# E103-W02.net
KiCad netlist of a schematic drawn in Altium Designer
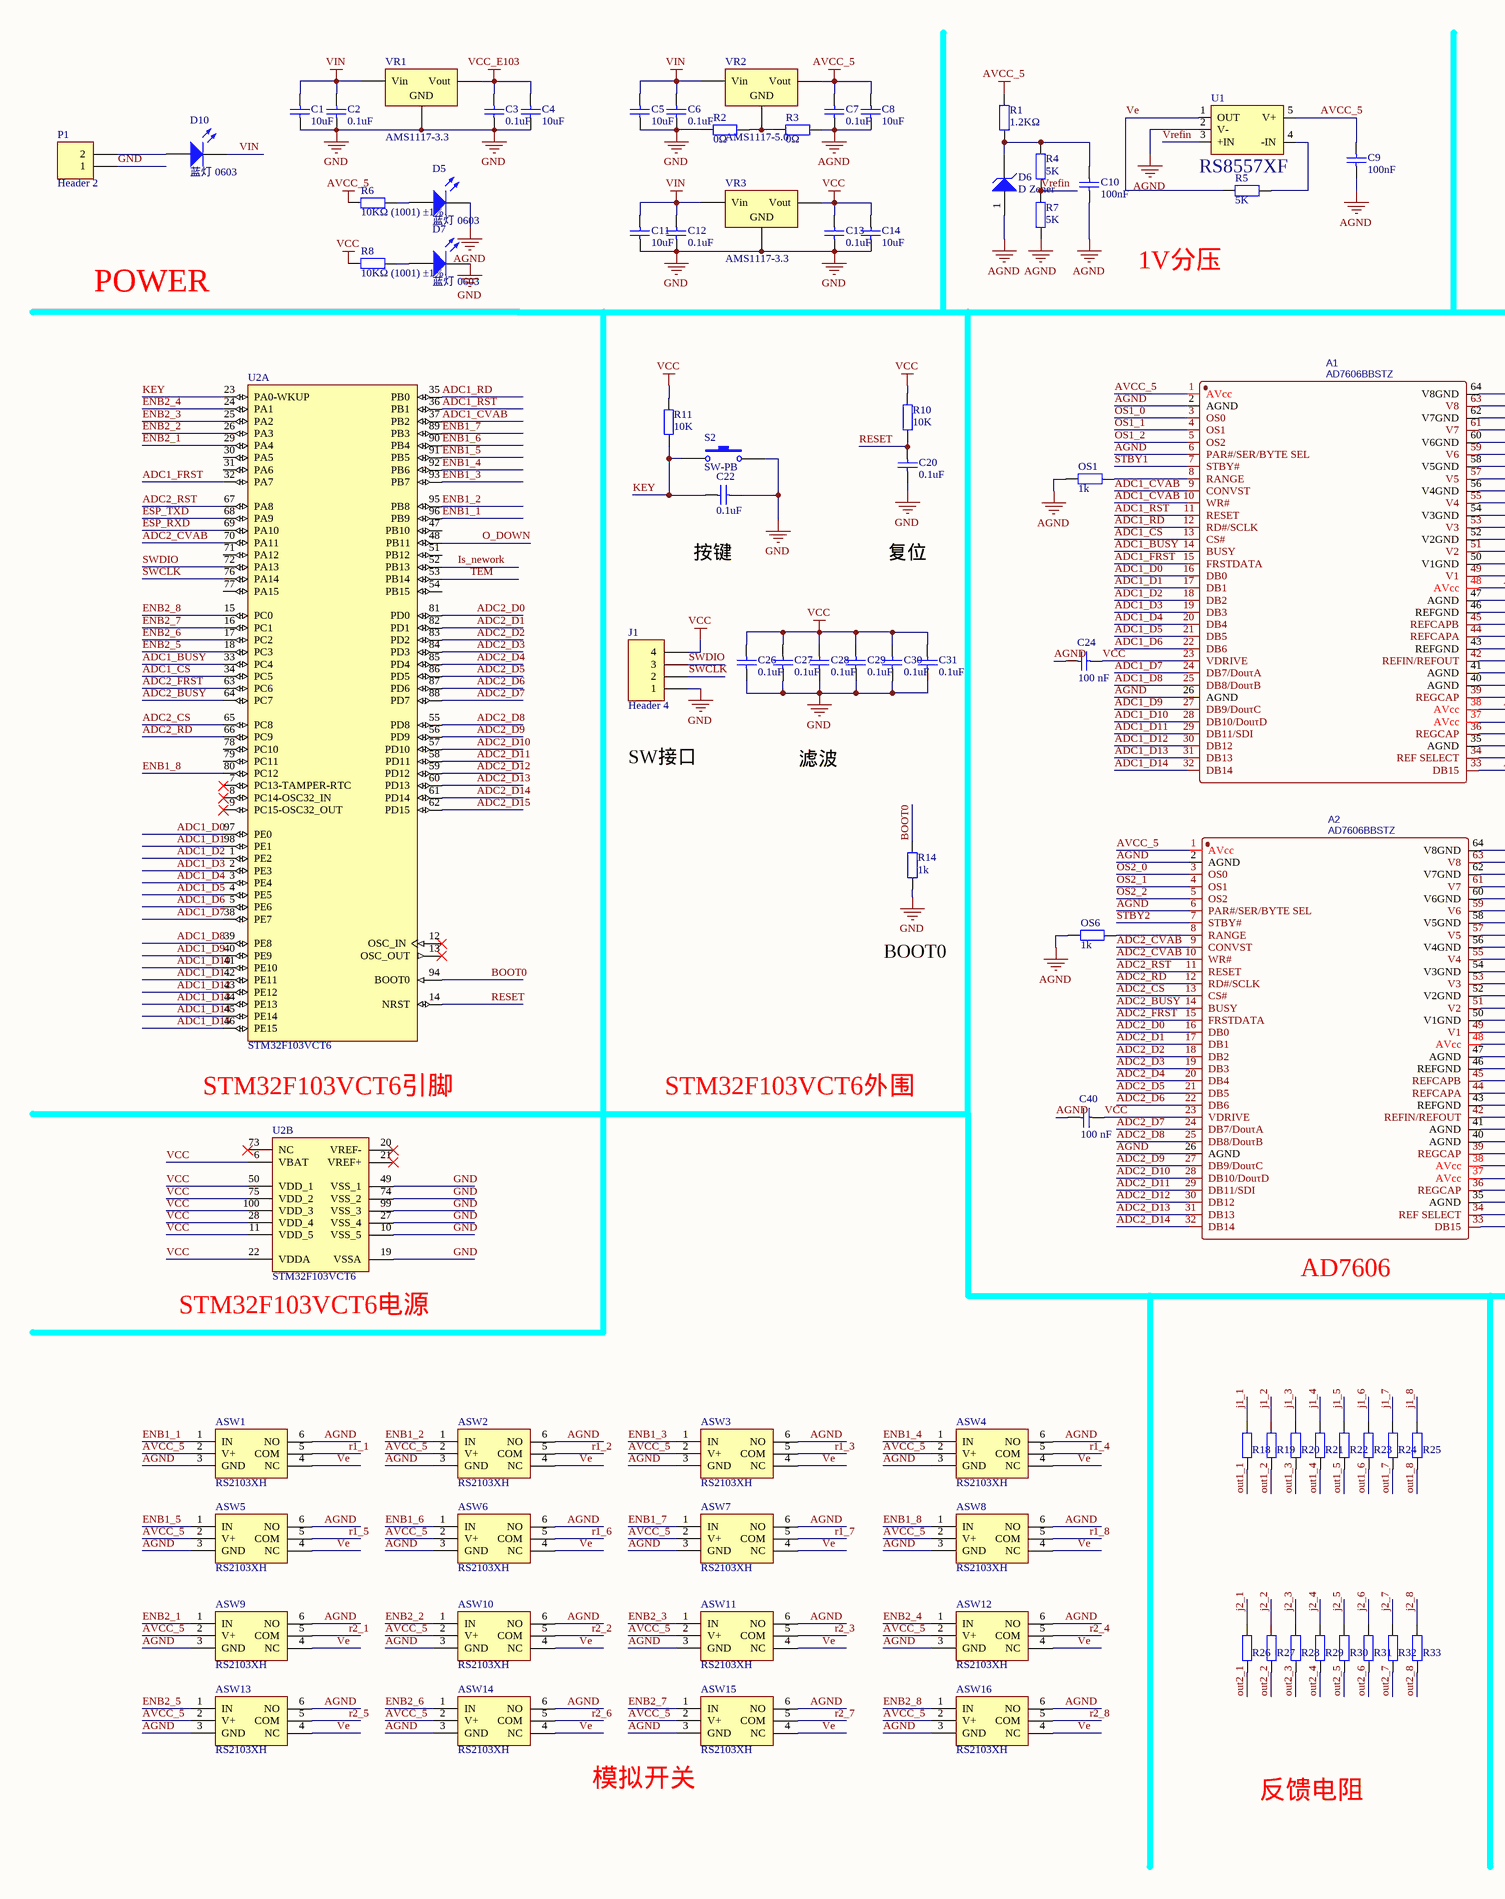
[diagram p0: E103-W02.SchDoc, left]
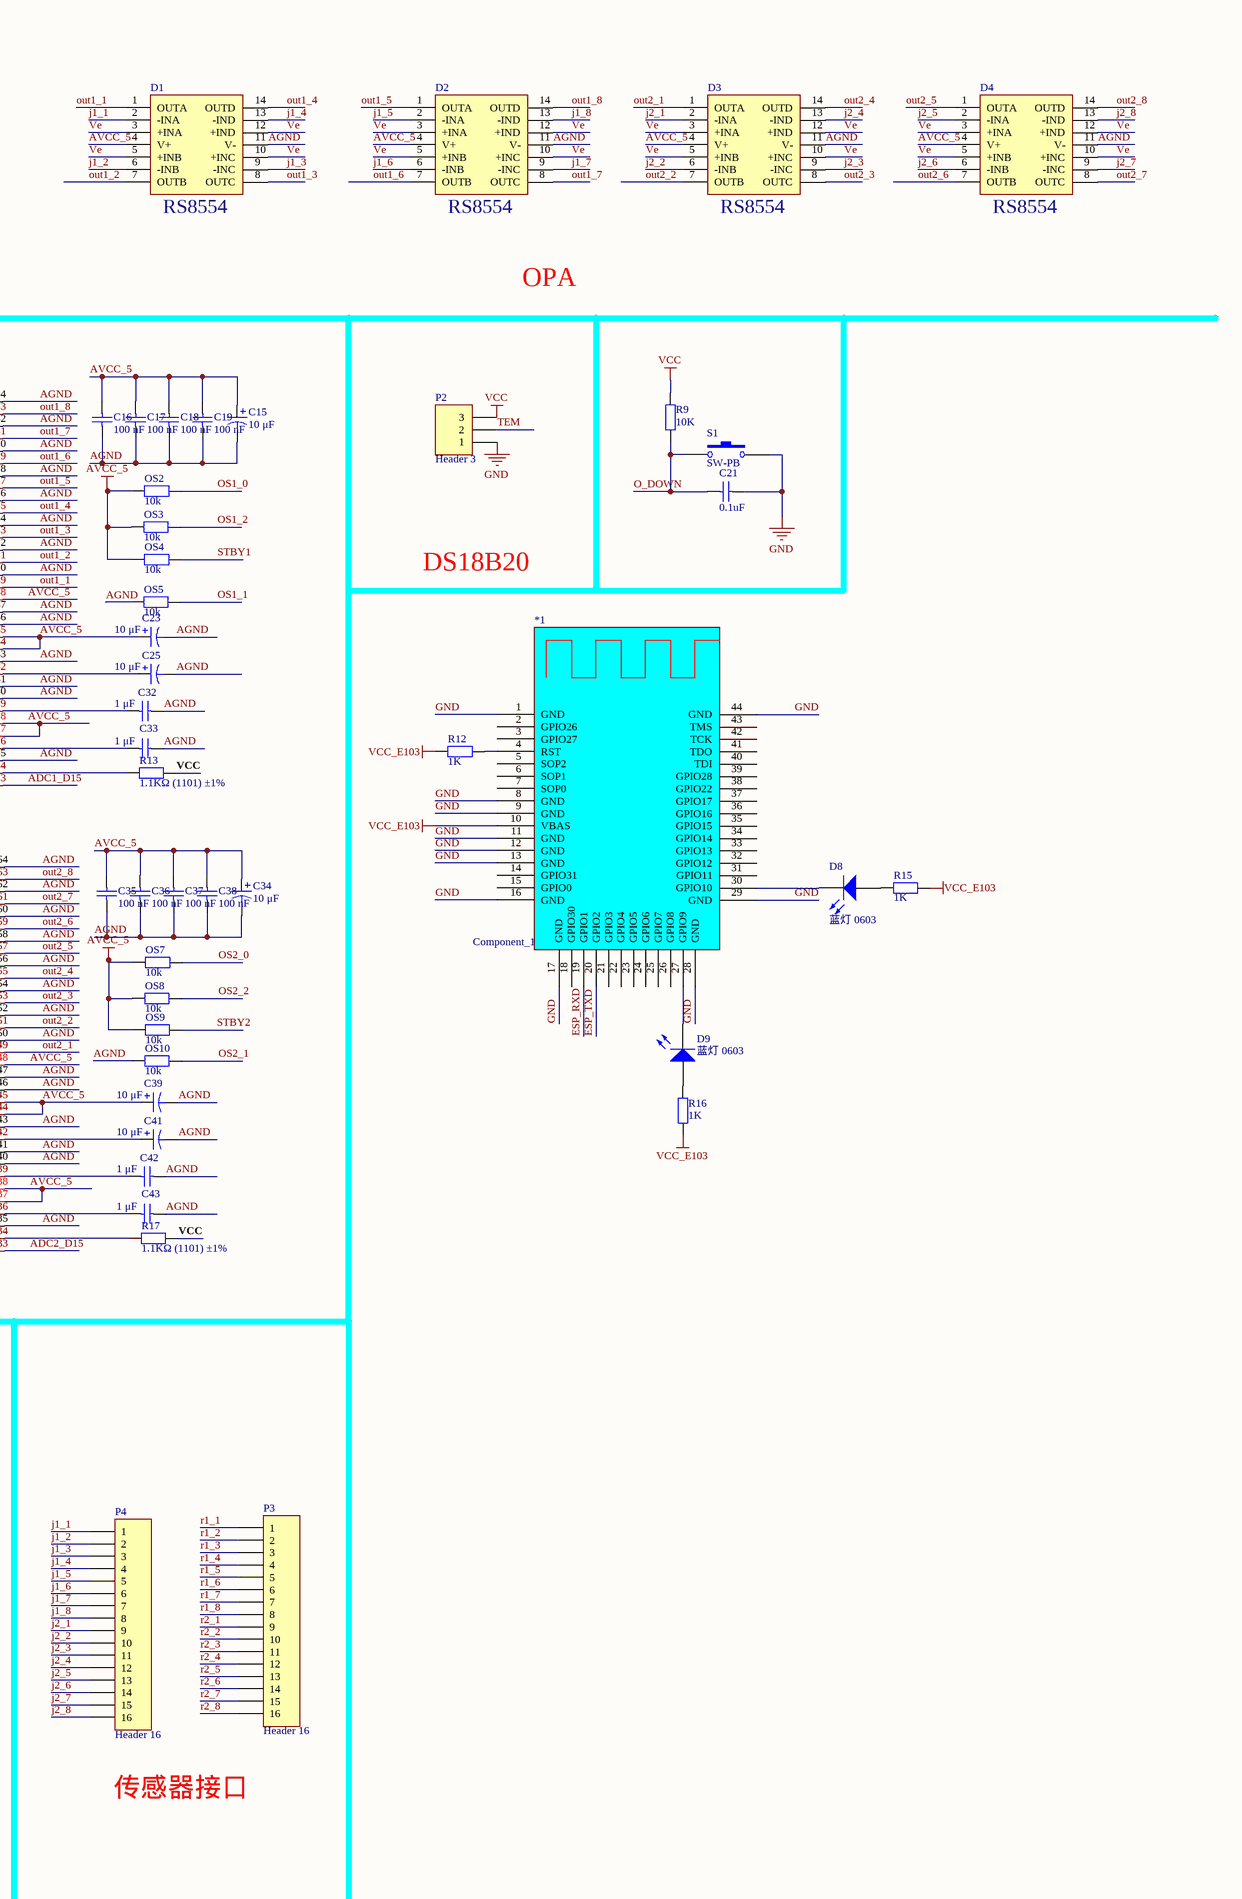
[diagram p1: E103-W02.SchDoc, right]

(export (version "E")
  (design (tool "Eeschema 10.0.6"))
  (components
    (comp (ref "*1")
      (value "Component_1")
      (footprint "E103-W02")
      (libsource (lib "Schlib1") (part "Component_1"))
    )
    (comp (ref "A1")
      (value "AD7606BBSTZ")
      (footprint "AD7606")
      (fields (field (name "BOM_SUPPLIER PART") "C443885") (field (name "CONTRIBUTOR") "LCSC"))
      (libsource (lib "altium-import") (part "root_0_AD7606BBSTZ_"))
    )
    (comp (ref "A2")
      (value "AD7606BBSTZ")
      (footprint "AD7606")
      (fields (field (name "BOM_SUPPLIER PART") "C443885") (field (name "CONTRIBUTOR") "LCSC"))
      (libsource (lib "altium-import") (part "root_0_AD7606BBSTZ_"))
    )
    (comp (ref "ASW1")
      (value "RS2103XH")
      (footprint "SOT-23-6")
      (libsource (lib "common_Schlib") (part "RS2103XH"))
    )
    (comp (ref "ASW2")
      (value "RS2103XH")
      (footprint "SOT-23-6")
      (libsource (lib "common_Schlib") (part "RS2103XH"))
    )
    (comp (ref "ASW3")
      (value "RS2103XH")
      (footprint "SOT-23-6")
      (libsource (lib "common_Schlib") (part "RS2103XH"))
    )
    (comp (ref "ASW4")
      (value "RS2103XH")
      (footprint "SOT-23-6")
      (libsource (lib "common_Schlib") (part "RS2103XH"))
    )
    (comp (ref "ASW5")
      (value "RS2103XH")
      (footprint "SOT-23-6")
      (libsource (lib "common_Schlib") (part "RS2103XH"))
    )
    (comp (ref "ASW6")
      (value "RS2103XH")
      (footprint "SOT-23-6")
      (libsource (lib "common_Schlib") (part "RS2103XH"))
    )
    (comp (ref "ASW7")
      (value "RS2103XH")
      (footprint "SOT-23-6")
      (libsource (lib "common_Schlib") (part "RS2103XH"))
    )
    (comp (ref "ASW8")
      (value "RS2103XH")
      (footprint "SOT-23-6")
      (libsource (lib "common_Schlib") (part "RS2103XH"))
    )
    (comp (ref "ASW9")
      (value "RS2103XH")
      (footprint "SOT-23-6")
      (libsource (lib "common_Schlib") (part "RS2103XH"))
    )
    (comp (ref "ASW10")
      (value "RS2103XH")
      (footprint "SOT-23-6")
      (libsource (lib "common_Schlib") (part "RS2103XH"))
    )
    (comp (ref "ASW11")
      (value "RS2103XH")
      (footprint "SOT-23-6")
      (libsource (lib "common_Schlib") (part "RS2103XH"))
    )
    (comp (ref "ASW12")
      (value "RS2103XH")
      (footprint "SOT-23-6")
      (libsource (lib "common_Schlib") (part "RS2103XH"))
    )
    (comp (ref "ASW13")
      (value "RS2103XH")
      (footprint "SOT-23-6")
      (libsource (lib "common_Schlib") (part "RS2103XH"))
    )
    (comp (ref "ASW14")
      (value "RS2103XH")
      (footprint "SOT-23-6")
      (libsource (lib "common_Schlib") (part "RS2103XH"))
    )
    (comp (ref "ASW15")
      (value "RS2103XH")
      (footprint "SOT-23-6")
      (libsource (lib "common_Schlib") (part "RS2103XH"))
    )
    (comp (ref "ASW16")
      (value "RS2103XH")
      (footprint "SOT-23-6")
      (libsource (lib "common_Schlib") (part "RS2103XH"))
    )
    (comp (ref "C1")
      (value "10uF")
      (footprint "0603_C")
      (description "贴片电容")
      (libsource (lib "Miscellaneous Devices LC") (part "0603 1.0pF (010) 0.25pF 50V"))
    )
    (comp (ref "C2")
      (value "0.1uF")
      (footprint "0603_C")
      (description "贴片电容")
      (libsource (lib "Miscellaneous Devices LC") (part "0603 1.0pF (010) 0.25pF 50V"))
    )
    (comp (ref "C3")
      (value "0.1uF")
      (footprint "0603_C")
      (description "贴片电容")
      (libsource (lib "Miscellaneous Devices LC") (part "0603 1.0pF (010) 0.25pF 50V"))
    )
    (comp (ref "C4")
      (value "10uF")
      (footprint "0603_C")
      (description "贴片电容")
      (libsource (lib "Miscellaneous Devices LC") (part "0603 1.0pF (010) 0.25pF 50V"))
    )
    (comp (ref "C5")
      (value "10uF")
      (footprint "0603_C")
      (description "贴片电容")
      (libsource (lib "Miscellaneous Devices LC") (part "0603 1.0pF (010) 0.25pF 50V"))
    )
    (comp (ref "C6")
      (value "0.1uF")
      (footprint "0603_C")
      (description "贴片电容")
      (libsource (lib "Miscellaneous Devices LC") (part "0603 1.0pF (010) 0.25pF 50V"))
    )
    (comp (ref "C7")
      (value "0.1uF")
      (footprint "0603_C")
      (description "贴片电容")
      (libsource (lib "Miscellaneous Devices LC") (part "0603 1.0pF (010) 0.25pF 50V"))
    )
    (comp (ref "C8")
      (value "10uF")
      (footprint "0603_C")
      (description "贴片电容")
      (libsource (lib "Miscellaneous Devices LC") (part "0603 1.0pF (010) 0.25pF 50V"))
    )
    (comp (ref "C9")
      (value "100nF")
      (footprint "0603_C")
      (description "贴片电容")
      (libsource (lib "Miscellaneous Devices LC") (part "0402 100nF (104) 10% 16V"))
    )
    (comp (ref "C10")
      (value "100nF")
      (footprint "0603_C")
      (description "贴片电容")
      (libsource (lib "Miscellaneous Devices LC") (part "0402 100nF (104) 10% 16V"))
    )
    (comp (ref "C11")
      (value "10uF")
      (footprint "0603_C")
      (description "贴片电容")
      (libsource (lib "Miscellaneous Devices LC") (part "0603 1.0pF (010) 0.25pF 50V"))
    )
    (comp (ref "C12")
      (value "0.1uF")
      (footprint "0603_C")
      (description "贴片电容")
      (libsource (lib "Miscellaneous Devices LC") (part "0603 1.0pF (010) 0.25pF 50V"))
    )
    (comp (ref "C13")
      (value "0.1uF")
      (footprint "0603_C")
      (description "贴片电容")
      (libsource (lib "Miscellaneous Devices LC") (part "0603 1.0pF (010) 0.25pF 50V"))
    )
    (comp (ref "C14")
      (value "10uF")
      (footprint "0603_C")
      (description "贴片电容")
      (libsource (lib "Miscellaneous Devices LC") (part "0603 1.0pF (010) 0.25pF 50V"))
    )
    (comp (ref "C15")
      (value "10 μF")
      (footprint "CASE-A_3216")
      (description "Polarized Capacitor (Surface Mount)")
      (fields (field (name "Comment") "Cap Pol3") (field (name "PUBLISHER") "Altium Limited"))
      (libsource (lib "Miscellaneous Devices") (part "Cap Pol3"))
    )
    (comp (ref "C16")
      (value "100 nF")
      (footprint "0603_C")
      (description "贴片电容")
      (libsource (lib "Miscellaneous Devices LC") (part "0603 1.5nF (152) 10% 50V"))
    )
    (comp (ref "C17")
      (value "100 nF")
      (footprint "0603_C")
      (description "贴片电容")
      (libsource (lib "Miscellaneous Devices LC") (part "0603 1.5nF (152) 10% 50V"))
    )
    (comp (ref "C18")
      (value "100 nF")
      (footprint "0603_C")
      (description "贴片电容")
      (libsource (lib "Miscellaneous Devices LC") (part "0603 1.5nF (152) 10% 50V"))
    )
    (comp (ref "C19")
      (value "100 nF")
      (footprint "0603_C")
      (description "贴片电容")
      (libsource (lib "Miscellaneous Devices LC") (part "0603 1.5nF (152) 10% 50V"))
    )
    (comp (ref "C20")
      (value "0.1uF")
      (footprint "0603_C")
      (description "贴片电容")
      (libsource (lib "Miscellaneous Devices LC") (part "0402 100nF (104) 10% 16V"))
    )
    (comp (ref "C21")
      (value "0.1uF")
      (footprint "0603_C")
      (description "贴片电容")
      (libsource (lib "Miscellaneous Devices LC") (part "0402 100nF (104) 10% 16V"))
    )
    (comp (ref "C22")
      (value "0.1uF")
      (footprint "0603_C")
      (description "贴片电容")
      (libsource (lib "Miscellaneous Devices LC") (part "0402 100nF (104) 10% 16V"))
    )
    (comp (ref "C23")
      (value "10 μF")
      (footprint "CASE-A_3216")
      (description "Polarized Capacitor (Surface Mount)")
      (fields (field (name "Comment") "Cap Pol3") (field (name "PUBLISHER") "Altium Limited"))
      (libsource (lib "Miscellaneous Devices") (part "Cap Pol3"))
    )
    (comp (ref "C24")
      (value "100 nF")
      (footprint "0603_C")
      (description "贴片电容")
      (libsource (lib "Miscellaneous Devices LC") (part "0603 1.5nF (152) 10% 50V"))
    )
    (comp (ref "C25")
      (value "10 μF")
      (footprint "CASE-A_3216")
      (description "Polarized Capacitor (Surface Mount)")
      (fields (field (name "Comment") "Cap Pol3") (field (name "PUBLISHER") "Altium Limited"))
      (libsource (lib "Miscellaneous Devices") (part "Cap Pol3"))
    )
    (comp (ref "C26")
      (value "0.1uF")
      (footprint "0603_C")
      (description "贴片电容")
      (libsource (lib "Miscellaneous Devices LC") (part "0402 1.0uF (105) 10% 25V"))
    )
    (comp (ref "C27")
      (value "0.1uF")
      (footprint "0603_C")
      (description "贴片电容")
      (libsource (lib "Miscellaneous Devices LC") (part "0402 1.0uF (105) 10% 25V"))
    )
    (comp (ref "C28")
      (value "0.1uF")
      (footprint "0603_C")
      (description "贴片电容")
      (libsource (lib "Miscellaneous Devices LC") (part "0402 1.0uF (105) 10% 25V"))
    )
    (comp (ref "C29")
      (value "0.1uF")
      (footprint "0603_C")
      (description "贴片电容")
      (libsource (lib "Miscellaneous Devices LC") (part "0402 1.0uF (105) 10% 25V"))
    )
    (comp (ref "C30")
      (value "0.1uF")
      (footprint "0603_C")
      (description "贴片电容")
      (libsource (lib "Miscellaneous Devices LC") (part "0402 1.0uF (105) 10% 25V"))
    )
    (comp (ref "C31")
      (value "0.1uF")
      (footprint "0603_C")
      (description "贴片电容")
      (libsource (lib "Miscellaneous Devices LC") (part "0402 1.0uF (105) 10% 25V"))
    )
    (comp (ref "C32")
      (value "1 μF")
      (footprint "0603_C")
      (description "贴片电容")
      (libsource (lib "Miscellaneous Devices LC") (part "0603 1.5nF (152) 10% 50V"))
    )
    (comp (ref "C33")
      (value "1 μF")
      (footprint "0603_C")
      (description "贴片电容")
      (libsource (lib "Miscellaneous Devices LC") (part "0603 1.5nF (152) 10% 50V"))
    )
    (comp (ref "C34")
      (value "10 μF")
      (footprint "CASE-A_3216")
      (description "Polarized Capacitor (Surface Mount)")
      (fields (field (name "Comment") "Cap Pol3") (field (name "PUBLISHER") "Altium Limited"))
      (libsource (lib "Miscellaneous Devices") (part "Cap Pol3"))
    )
    (comp (ref "C35")
      (value "100 nF")
      (footprint "0603_C")
      (description "贴片电容")
      (libsource (lib "Miscellaneous Devices LC") (part "0603 1.5nF (152) 10% 50V"))
    )
    (comp (ref "C36")
      (value "100 nF")
      (footprint "0603_C")
      (description "贴片电容")
      (libsource (lib "Miscellaneous Devices LC") (part "0603 1.5nF (152) 10% 50V"))
    )
    (comp (ref "C37")
      (value "100 nF")
      (footprint "0603_C")
      (description "贴片电容")
      (libsource (lib "Miscellaneous Devices LC") (part "0603 1.5nF (152) 10% 50V"))
    )
    (comp (ref "C38")
      (value "100 nF")
      (footprint "0603_C")
      (description "贴片电容")
      (libsource (lib "Miscellaneous Devices LC") (part "0603 1.5nF (152) 10% 50V"))
    )
    (comp (ref "C39")
      (value "10 μF")
      (footprint "CASE-A_3216")
      (description "Polarized Capacitor (Surface Mount)")
      (fields (field (name "Comment") "Cap Pol3") (field (name "PUBLISHER") "Altium Limited"))
      (libsource (lib "Miscellaneous Devices") (part "Cap Pol3"))
    )
    (comp (ref "C40")
      (value "100 nF")
      (footprint "0603_C")
      (description "贴片电容")
      (libsource (lib "Miscellaneous Devices LC") (part "0603 1.5nF (152) 10% 50V"))
    )
    (comp (ref "C41")
      (value "10 μF")
      (footprint "CASE-A_3216")
      (description "Polarized Capacitor (Surface Mount)")
      (fields (field (name "Comment") "Cap Pol3") (field (name "PUBLISHER") "Altium Limited"))
      (libsource (lib "Miscellaneous Devices") (part "Cap Pol3"))
    )
    (comp (ref "C42")
      (value "1 μF")
      (footprint "0603_C")
      (description "贴片电容")
      (libsource (lib "Miscellaneous Devices LC") (part "0603 1.5nF (152) 10% 50V"))
    )
    (comp (ref "C43")
      (value "1 μF")
      (footprint "0603_C")
      (description "贴片电容")
      (libsource (lib "Miscellaneous Devices LC") (part "0603 1.5nF (152) 10% 50V"))
    )
    (comp (ref "D1")
      (value "RS8554")
      (footprint "RS8554")
      (description "运放，4个集成IC，轨至轨，2.3-5.5V，SOIC-14和TSSOP-14封装")
      (libsource (lib "common_Schlib") (part "运放_OPA4374"))
    )
    (comp (ref "D2")
      (value "RS8554")
      (footprint "RS8554")
      (description "运放，4个集成IC，轨至轨，2.3-5.5V，SOIC-14和TSSOP-14封装")
      (libsource (lib "common_Schlib") (part "运放_OPA4374"))
    )
    (comp (ref "D3")
      (value "RS8554")
      (footprint "RS8554")
      (description "运放，4个集成IC，轨至轨，2.3-5.5V，SOIC-14和TSSOP-14封装")
      (libsource (lib "common_Schlib") (part "运放_OPA4374"))
    )
    (comp (ref "D4")
      (value "RS8554")
      (footprint "RS8554")
      (description "运放，4个集成IC，轨至轨，2.3-5.5V，SOIC-14和TSSOP-14封装")
      (libsource (lib "common_Schlib") (part "运放_OPA4374"))
    )
    (comp (ref "D5")
      (value "蓝灯 0603")
      (footprint "0603_LED_S1")
      (description "发光二极管")
      (libsource (lib "Miscellaneous Devices LC") (part "0603 蓝灯"))
    )
    (comp (ref "D6")
      (value "D Zener")
      (footprint "SOT-23(SOT-23-3)")
      (description "Zener Diode")
      (fields (field (name "PUBLISHER") "Altium Limited"))
      (libsource (lib "Miscellaneous Devices") (part "D Zener"))
    )
    (comp (ref "D7")
      (value "蓝灯 0603")
      (footprint "0603_LED_S1")
      (description "发光二极管")
      (libsource (lib "Miscellaneous Devices LC") (part "0603 蓝灯"))
    )
    (comp (ref "D8")
      (value "蓝灯 0603")
      (footprint "0603_LED_S1")
      (description "发光二极管")
      (libsource (lib "Miscellaneous Devices LC") (part "0603 蓝灯"))
    )
    (comp (ref "D9")
      (value "蓝灯 0603")
      (footprint "0603_LED_S1")
      (description "发光二极管")
      (libsource (lib "Miscellaneous Devices LC") (part "0603 蓝灯"))
    )
    (comp (ref "D10")
      (value "蓝灯 0603")
      (footprint "标准DO-214AC")
      (description "发光二极管")
      (libsource (lib "Miscellaneous Devices LC") (part "0603 蓝灯"))
    )
    (comp (ref "J1")
      (value "Header 4")
      (footprint "HDR1X4")
      (description "Header, 4-Pin")
      (fields (field (name "PUBLISHER") "Altium Limited"))
      (libsource (lib "Miscellaneous Connectors") (part "Header 4"))
    )
    (comp (ref "OS1")
      (value "1k")
      (footprint "0603_C")
      (description "贴片电阻")
      (libsource (lib "Miscellaneous Devices LC") (part "0603 0Ω (0R0) 1%"))
    )
    (comp (ref "OS2")
      (value "10k")
      (footprint "0603_C")
      (description "贴片电阻")
      (libsource (lib "Miscellaneous Devices LC") (part "0603 0Ω (0R0) 1%"))
    )
    (comp (ref "OS3")
      (value "10k")
      (footprint "0603_C")
      (description "贴片电阻")
      (libsource (lib "Miscellaneous Devices LC") (part "0603 0Ω (0R0) 1%"))
    )
    (comp (ref "OS4")
      (value "10k")
      (footprint "0603_C")
      (description "贴片电阻")
      (libsource (lib "Miscellaneous Devices LC") (part "0603 0Ω (0R0) 1%"))
    )
    (comp (ref "OS5")
      (value "10k")
      (footprint "0603_C")
      (description "贴片电阻")
      (libsource (lib "Miscellaneous Devices LC") (part "0603 0Ω (0R0) 1%"))
    )
    (comp (ref "OS6")
      (value "1k")
      (footprint "0603_C")
      (description "贴片电阻")
      (libsource (lib "Miscellaneous Devices LC") (part "0603 0Ω (0R0) 1%"))
    )
    (comp (ref "OS7")
      (value "10k")
      (footprint "0603_C")
      (description "贴片电阻")
      (libsource (lib "Miscellaneous Devices LC") (part "0603 0Ω (0R0) 1%"))
    )
    (comp (ref "OS8")
      (value "10k")
      (footprint "0603_C")
      (description "贴片电阻")
      (libsource (lib "Miscellaneous Devices LC") (part "0603 0Ω (0R0) 1%"))
    )
    (comp (ref "OS9")
      (value "10k")
      (footprint "0603_C")
      (description "贴片电阻")
      (libsource (lib "Miscellaneous Devices LC") (part "0603 0Ω (0R0) 1%"))
    )
    (comp (ref "OS10")
      (value "10k")
      (footprint "0603_C")
      (description "贴片电阻")
      (libsource (lib "Miscellaneous Devices LC") (part "0603 0Ω (0R0) 1%"))
    )
    (comp (ref "P1")
      (value "Header 2")
      (footprint "HDR1X2")
      (description "Header, 2-Pin")
      (fields (field (name "PUBLISHER") "Altium Limited"))
      (libsource (lib "Miscellaneous Connectors") (part "Header 2"))
    )
    (comp (ref "P2")
      (value "Header 3")
      (footprint "HDR1X3")
      (description "Header, 3-Pin")
      (fields (field (name "PUBLISHER") "Altium Limited"))
      (libsource (lib "Miscellaneous Connectors") (part "Header 3"))
    )
    (comp (ref "P3")
      (value "Header 16")
      (footprint "FPC_16_0.5")
      (description "Header, 16-Pin")
      (fields (field (name "PUBLISHER") "Altium Limited"))
      (libsource (lib "Miscellaneous Connectors") (part "Header 16"))
    )
    (comp (ref "P4")
      (value "Header 16")
      (footprint "FPC_16_0.5")
      (description "Header, 16-Pin")
      (fields (field (name "PUBLISHER") "Altium Limited"))
      (libsource (lib "Miscellaneous Connectors") (part "Header 16"))
    )
    (comp (ref "R1")
      (value "1.2KΩ")
      (footprint "0603_R")
      (description "贴片电阻")
      (libsource (lib "Miscellaneous Devices LC") (part "0402 1.2KΩ (1201) 1%"))
    )
    (comp (ref "R2")
      (value "0Ω")
      (footprint "0603_R")
      (description "贴片电阻")
      (libsource (lib "Miscellaneous Devices LC") (part "1206 0Ω (0R0) 1%"))
    )
    (comp (ref "R3")
      (value "0Ω")
      (footprint "0603_R")
      (description "贴片电阻")
      (libsource (lib "Miscellaneous Devices LC") (part "1206 0Ω (0R0) 1%"))
    )
    (comp (ref "R4")
      (value "5K")
      (footprint "0603_R")
      (description "贴片电阻")
      (libsource (lib "") (part "0603 100Ω (1000) 1%_2"))
    )
    (comp (ref "R5")
      (value "5K")
      (footprint "0603_R")
      (description "贴片电阻")
      (libsource (lib "") (part "0603 100Ω (1000) 1%_1"))
    )
    (comp (ref "R6")
      (value "10KΩ (1001) ±1%")
      (footprint "0603_R")
      (description "贴片电阻")
      (libsource (lib "Miscellaneous Devices LC") (part "0402 1KΩ (1001) 1%"))
    )
    (comp (ref "R7")
      (value "5K")
      (footprint "0603_R")
      (description "贴片电阻")
      (libsource (lib "Miscellaneous Devices LC") (part "0603 100Ω (1000) 1%"))
    )
    (comp (ref "R8")
      (value "10KΩ (1001) ±1%")
      (footprint "0603_R")
      (description "贴片电阻")
      (libsource (lib "Miscellaneous Devices LC") (part "0402 1KΩ (1001) 1%"))
    )
    (comp (ref "R9")
      (value "10K")
      (footprint "0603_R")
      (description "贴片电阻")
      (libsource (lib "Miscellaneous Devices LC") (part "0402 10KΩ (1002) 1%"))
    )
    (comp (ref "R10")
      (value "10K")
      (footprint "0603_R")
      (description "贴片电阻")
      (libsource (lib "Miscellaneous Devices LC") (part "0402 10KΩ (1002) 1%"))
    )
    (comp (ref "R11")
      (value "10K")
      (footprint "0603_R")
      (description "贴片电阻")
      (libsource (lib "Miscellaneous Devices LC") (part "0402 10KΩ (1002) 1%"))
    )
    (comp (ref "R12")
      (value "1K")
      (footprint "0603_C")
      (description "贴片电阻")
      (libsource (lib "Miscellaneous Devices LC") (part "0603 1.1KΩ (1101) 1%"))
    )
    (comp (ref "R13")
      (value "1.1KΩ (1101) ±1%")
      (footprint "0603_C")
      (description "贴片电阻")
      (libsource (lib "Miscellaneous Devices LC") (part "0603 1.1KΩ (1101) 1%"))
    )
    (comp (ref "R14")
      (value "1k")
      (footprint "0603_R")
      (description "贴片电阻")
      (libsource (lib "Miscellaneous Devices LC") (part "0402 0Ω (0R0) 1%"))
    )
    (comp (ref "R15")
      (value "1K")
      (footprint "0603_R")
      (description "贴片电阻")
      (libsource (lib "") (part "0402 10KΩ (1002) 1%_1"))
    )
    (comp (ref "R16")
      (value "1K")
      (footprint "0603_R")
      (description "贴片电阻")
      (libsource (lib "Miscellaneous Devices LC") (part "0402 10KΩ (1002) 1%"))
    )
    (comp (ref "R17")
      (value "1.1KΩ (1101) ±1%")
      (footprint "0603_C")
      (description "贴片电阻")
      (libsource (lib "Miscellaneous Devices LC") (part "0603 1.1KΩ (1101) 1%"))
    )
    (comp (ref "R18")
      (value "100Ω")
      (footprint "0603_R")
      (description "贴片电阻")
      (libsource (lib "Miscellaneous Devices LC") (part "0603 2KΩ (2001) 1%"))
    )
    (comp (ref "R19")
      (value "100Ω")
      (footprint "0603_R")
      (description "贴片电阻")
      (libsource (lib "Miscellaneous Devices LC") (part "0603 2KΩ (2001) 1%"))
    )
    (comp (ref "R20")
      (value "100Ω")
      (footprint "0603_R")
      (description "贴片电阻")
      (libsource (lib "Miscellaneous Devices LC") (part "0603 2KΩ (2001) 1%"))
    )
    (comp (ref "R21")
      (value "100Ω")
      (footprint "0603_R")
      (description "贴片电阻")
      (libsource (lib "Miscellaneous Devices LC") (part "0603 2KΩ (2001) 1%"))
    )
    (comp (ref "R22")
      (value "100Ω")
      (footprint "0603_R")
      (description "贴片电阻")
      (libsource (lib "Miscellaneous Devices LC") (part "0603 2KΩ (2001) 1%"))
    )
    (comp (ref "R23")
      (value "100Ω")
      (footprint "0603_R")
      (description "贴片电阻")
      (libsource (lib "Miscellaneous Devices LC") (part "0603 2KΩ (2001) 1%"))
    )
    (comp (ref "R24")
      (value "100Ω")
      (footprint "0603_R")
      (description "贴片电阻")
      (libsource (lib "Miscellaneous Devices LC") (part "0603 2KΩ (2001) 1%"))
    )
    (comp (ref "R25")
      (value "0KΩ")
      (footprint "0603_R")
      (description "贴片电阻")
      (libsource (lib "Miscellaneous Devices LC") (part "0603 2KΩ (2001) 1%"))
    )
    (comp (ref "R26")
      (value "100Ω")
      (footprint "0603_R")
      (description "贴片电阻")
      (libsource (lib "Miscellaneous Devices LC") (part "0603 2KΩ (2001) 1%"))
    )
    (comp (ref "R27")
      (value "100Ω")
      (footprint "0603_R")
      (description "贴片电阻")
      (libsource (lib "Miscellaneous Devices LC") (part "0603 2KΩ (2001) 1%"))
    )
    (comp (ref "R28")
      (value "100Ω")
      (footprint "0603_R")
      (description "贴片电阻")
      (libsource (lib "Miscellaneous Devices LC") (part "0603 2KΩ (2001) 1%"))
    )
    (comp (ref "R29")
      (value "100Ω")
      (footprint "0603_R")
      (description "贴片电阻")
      (libsource (lib "Miscellaneous Devices LC") (part "0603 2KΩ (2001) 1%"))
    )
    (comp (ref "R30")
      (value "100Ω")
      (footprint "0603_R")
      (description "贴片电阻")
      (libsource (lib "Miscellaneous Devices LC") (part "0603 2KΩ (2001) 1%"))
    )
    (comp (ref "R31")
      (value "100Ω")
      (footprint "0603_R")
      (description "贴片电阻")
      (libsource (lib "Miscellaneous Devices LC") (part "0603 2KΩ (2001) 1%"))
    )
    (comp (ref "R32")
      (value "100Ω")
      (footprint "0603_R")
      (description "贴片电阻")
      (libsource (lib "Miscellaneous Devices LC") (part "0603 2KΩ (2001) 1%"))
    )
    (comp (ref "R33")
      (value "0KΩ")
      (footprint "0603_R")
      (description "贴片电阻")
      (libsource (lib "Miscellaneous Devices LC") (part "0603 2KΩ (2001) 1%"))
    )
    (comp (ref "S1")
      (value "SW-PB")
      (footprint "按键")
      (description "Switch")
      (fields (field (name "PUBLISHER") "Altium Limited"))
      (libsource (lib "Miscellaneous Devices") (part "SW-PB"))
    )
    (comp (ref "S2")
      (value "SW-PB")
      (footprint "按键")
      (description "Switch")
      (fields (field (name "PUBLISHER") "Altium Limited"))
      (libsource (lib "Miscellaneous Devices") (part "SW-PB"))
    )
    (comp (ref "U1") (value "RS8557XF") (footprint "SOT-23-5") (libsource (lib "Schlib1") (part "RS8557XF")))
    (comp (ref "U2")
      (value "STM32F103VCT6")
      (footprint "LQFP-100_14x14x05P")
      (description "ARM")
      (libsource (lib "Miscellaneous Devices LC") (part "STM32F103VCT6"))
    )
    (comp (ref "VR1")
      (value "AMS1117-3.3")
      (footprint "SOT-223")
      (description "低压差线性稳压(LDO)")
      (libsource (lib "Miscellaneous Devices LC") (part "SOT-223 AMS1117-3.3"))
    )
    (comp (ref "VR2")
      (value "AMS1117-5.0")
      (footprint "SOT-223")
      (description "低压差线性稳压(LDO)")
      (libsource (lib "Miscellaneous Devices LC") (part "SOT-223 AMS1117-3.3"))
    )
    (comp (ref "VR3")
      (value "AMS1117-3.3")
      (footprint "SOT-223")
      (description "低压差线性稳压(LDO)")
      (libsource (lib "Miscellaneous Devices LC") (part "SOT-223 AMS1117-3.3"))
    )
  )
  (nets
    (net (code "1") (name "/ADC1_BUSY") (class "Default")
      (node (ref "A1") (pin "14") (pinfunction "BUSY_14") (pintype "passive"))
      (node (ref "U2") (pin "33") (pinfunction "PC4_33") (pintype "bidirectional"))
    )
    (net (code "2") (name "/ADC1_CS") (class "Default")
      (node (ref "A1") (pin "13") (pinfunction "CS#_13") (pintype "passive"))
      (node (ref "U2") (pin "34") (pinfunction "PC5_34") (pintype "bidirectional"))
    )
    (net (code "3") (name "/ADC1_CVAB") (class "Default")
      (node (ref "A1") (pin "10") (pinfunction "WR#_10") (pintype "passive"))
      (node (ref "A1") (pin "9") (pinfunction "CONVST_9") (pintype "passive"))
      (node (ref "U2") (pin "37") (pinfunction "PB2_37") (pintype "bidirectional"))
    )
    (net (code "4") (name "/ADC1_D0") (class "Default")
      (node (ref "A1") (pin "16") (pinfunction "DB0_16") (pintype "passive"))
      (node (ref "U2") (pin "97") (pinfunction "PE0_97") (pintype "bidirectional"))
    )
    (net (code "5") (name "/ADC1_D1") (class "Default")
      (node (ref "A1") (pin "17") (pinfunction "DB1_17") (pintype "passive"))
      (node (ref "U2") (pin "98") (pinfunction "PE1_98") (pintype "bidirectional"))
    )
    (net (code "6") (name "/ADC1_D2") (class "Default")
      (node (ref "A1") (pin "18") (pinfunction "DB2_18") (pintype "passive"))
      (node (ref "U2") (pin "1") (pinfunction "PE2_1") (pintype "bidirectional"))
    )
    (net (code "7") (name "/ADC1_D3") (class "Default")
      (node (ref "A1") (pin "19") (pinfunction "DB3_19") (pintype "passive"))
      (node (ref "U2") (pin "2") (pinfunction "PE3_2") (pintype "bidirectional"))
    )
    (net (code "8") (name "/ADC1_D4") (class "Default")
      (node (ref "A1") (pin "20") (pinfunction "DB4_20") (pintype "passive"))
      (node (ref "U2") (pin "3") (pinfunction "PE4_3") (pintype "bidirectional"))
    )
    (net (code "9") (name "/ADC1_D5") (class "Default")
      (node (ref "A1") (pin "21") (pinfunction "DB5_21") (pintype "passive"))
      (node (ref "U2") (pin "4") (pinfunction "PE5_4") (pintype "bidirectional"))
    )
    (net (code "10") (name "/ADC1_D6") (class "Default")
      (node (ref "A1") (pin "22") (pinfunction "DB6_22") (pintype "passive"))
      (node (ref "U2") (pin "5") (pinfunction "PE6_5") (pintype "bidirectional"))
    )
    (net (code "11") (name "/ADC1_D7") (class "Default")
      (node (ref "A1") (pin "24") (pinfunction "DB7/DouτA_24") (pintype "passive"))
      (node (ref "U2") (pin "38") (pinfunction "PE7_38") (pintype "bidirectional"))
    )
    (net (code "12") (name "/ADC1_D8") (class "Default")
      (node (ref "A1") (pin "25") (pinfunction "DB8/DouτB_25") (pintype "passive"))
      (node (ref "U2") (pin "39") (pinfunction "PE8_39") (pintype "bidirectional"))
    )
    (net (code "13") (name "/ADC1_D9") (class "Default")
      (node (ref "A1") (pin "27") (pinfunction "DB9/DouτC_27") (pintype "passive"))
      (node (ref "U2") (pin "40") (pinfunction "PE9_40") (pintype "bidirectional"))
    )
    (net (code "14") (name "/ADC1_D10") (class "Default")
      (node (ref "A1") (pin "28") (pinfunction "DB10/DouτD_28") (pintype "passive"))
      (node (ref "U2") (pin "41") (pinfunction "PE10_41") (pintype "bidirectional"))
    )
    (net (code "15") (name "/ADC1_D11") (class "Default")
      (node (ref "A1") (pin "29") (pinfunction "DB11/SDI_29") (pintype "passive"))
      (node (ref "U2") (pin "42") (pinfunction "PE11_42") (pintype "bidirectional"))
    )
    (net (code "16") (name "/ADC1_D12") (class "Default")
      (node (ref "A1") (pin "30") (pinfunction "DB12_30") (pintype "passive"))
      (node (ref "U2") (pin "43") (pinfunction "PE12_43") (pintype "bidirectional"))
    )
    (net (code "17") (name "/ADC1_D13") (class "Default")
      (node (ref "A1") (pin "31") (pinfunction "DB13_31") (pintype "passive"))
      (node (ref "U2") (pin "44") (pinfunction "PE13_44") (pintype "bidirectional"))
    )
    (net (code "18") (name "/ADC1_D14") (class "Default")
      (node (ref "A1") (pin "32") (pinfunction "DB14_32") (pintype "passive"))
      (node (ref "U2") (pin "45") (pinfunction "PE14_45") (pintype "bidirectional"))
    )
    (net (code "19") (name "/ADC1_D15") (class "Default")
      (node (ref "A1") (pin "33") (pinfunction "DB15_33") (pintype "passive"))
      (node (ref "U2") (pin "46") (pinfunction "PE15_46") (pintype "bidirectional"))
    )
    (net (code "20") (name "/ADC1_FRST") (class "Default")
      (node (ref "A1") (pin "15") (pinfunction "FRSTDATA_15") (pintype "passive"))
      (node (ref "U2") (pin "32") (pinfunction "PA7_32") (pintype "bidirectional"))
    )
    (net (code "21") (name "/ADC1_RD") (class "Default")
      (node (ref "A1") (pin "12") (pinfunction "RD#/SCLK_12") (pintype "passive"))
      (node (ref "U2") (pin "35") (pinfunction "PB0_35") (pintype "bidirectional"))
    )
    (net (code "22") (name "/ADC1_RST") (class "Default")
      (node (ref "A1") (pin "11") (pinfunction "RESET_11") (pintype "passive"))
      (node (ref "U2") (pin "36") (pinfunction "PB1_36") (pintype "bidirectional"))
    )
    (net (code "23") (name "/ADC2_BUSY") (class "Default")
      (node (ref "A2") (pin "14") (pinfunction "BUSY_14") (pintype "passive"))
      (node (ref "U2") (pin "64") (pinfunction "PC7_64") (pintype "bidirectional"))
    )
    (net (code "24") (name "/ADC2_CS") (class "Default")
      (node (ref "A2") (pin "13") (pinfunction "CS#_13") (pintype "passive"))
      (node (ref "U2") (pin "65") (pinfunction "PC8_65") (pintype "bidirectional"))
    )
    (net (code "25") (name "/ADC2_CVAB") (class "Default")
      (node (ref "A2") (pin "10") (pinfunction "WR#_10") (pintype "passive"))
      (node (ref "A2") (pin "9") (pinfunction "CONVST_9") (pintype "passive"))
      (node (ref "U2") (pin "70") (pinfunction "PA11_70") (pintype "bidirectional"))
    )
    (net (code "26") (name "/ADC2_D0") (class "Default")
      (node (ref "A2") (pin "16") (pinfunction "DB0_16") (pintype "passive"))
      (node (ref "U2") (pin "81") (pinfunction "PD0_81") (pintype "bidirectional"))
    )
    (net (code "27") (name "/ADC2_D1") (class "Default")
      (node (ref "A2") (pin "17") (pinfunction "DB1_17") (pintype "passive"))
      (node (ref "U2") (pin "82") (pinfunction "PD1_82") (pintype "bidirectional"))
    )
    (net (code "28") (name "/ADC2_D2") (class "Default")
      (node (ref "A2") (pin "18") (pinfunction "DB2_18") (pintype "passive"))
      (node (ref "U2") (pin "83") (pinfunction "PD2_83") (pintype "bidirectional"))
    )
    (net (code "29") (name "/ADC2_D3") (class "Default")
      (node (ref "A2") (pin "19") (pinfunction "DB3_19") (pintype "passive"))
      (node (ref "U2") (pin "84") (pinfunction "PD3_84") (pintype "bidirectional"))
    )
    (net (code "30") (name "/ADC2_D4") (class "Default")
      (node (ref "A2") (pin "20") (pinfunction "DB4_20") (pintype "passive"))
      (node (ref "U2") (pin "85") (pinfunction "PD4_85") (pintype "bidirectional"))
    )
    (net (code "31") (name "/ADC2_D5") (class "Default")
      (node (ref "A2") (pin "21") (pinfunction "DB5_21") (pintype "passive"))
      (node (ref "U2") (pin "86") (pinfunction "PD5_86") (pintype "bidirectional"))
    )
    (net (code "32") (name "/ADC2_D6") (class "Default")
      (node (ref "A2") (pin "22") (pinfunction "DB6_22") (pintype "passive"))
      (node (ref "U2") (pin "87") (pinfunction "PD6_87") (pintype "bidirectional"))
    )
    (net (code "33") (name "/ADC2_D7") (class "Default")
      (node (ref "A2") (pin "24") (pinfunction "DB7/DouτA_24") (pintype "passive"))
      (node (ref "U2") (pin "88") (pinfunction "PD7_88") (pintype "bidirectional"))
    )
    (net (code "34") (name "/ADC2_D8") (class "Default")
      (node (ref "A2") (pin "25") (pinfunction "DB8/DouτB_25") (pintype "passive"))
      (node (ref "U2") (pin "55") (pinfunction "PD8_55") (pintype "bidirectional"))
    )
    (net (code "35") (name "/ADC2_D9") (class "Default")
      (node (ref "A2") (pin "27") (pinfunction "DB9/DouτC_27") (pintype "passive"))
      (node (ref "U2") (pin "56") (pinfunction "PD9_56") (pintype "bidirectional"))
    )
    (net (code "36") (name "/ADC2_D10") (class "Default")
      (node (ref "A2") (pin "28") (pinfunction "DB10/DouτD_28") (pintype "passive"))
      (node (ref "U2") (pin "57") (pinfunction "PD10_57") (pintype "bidirectional"))
    )
    (net (code "37") (name "/ADC2_D11") (class "Default")
      (node (ref "A2") (pin "29") (pinfunction "DB11/SDI_29") (pintype "passive"))
      (node (ref "U2") (pin "58") (pinfunction "PD11_58") (pintype "bidirectional"))
    )
    (net (code "38") (name "/ADC2_D12") (class "Default")
      (node (ref "A2") (pin "30") (pinfunction "DB12_30") (pintype "passive"))
      (node (ref "U2") (pin "59") (pinfunction "PD12_59") (pintype "bidirectional"))
    )
    (net (code "39") (name "/ADC2_D13") (class "Default")
      (node (ref "A2") (pin "31") (pinfunction "DB13_31") (pintype "passive"))
      (node (ref "U2") (pin "60") (pinfunction "PD13_60") (pintype "bidirectional"))
    )
    (net (code "40") (name "/ADC2_D14") (class "Default")
      (node (ref "A2") (pin "32") (pinfunction "DB14_32") (pintype "passive"))
      (node (ref "U2") (pin "61") (pinfunction "PD14_61") (pintype "bidirectional"))
    )
    (net (code "41") (name "/ADC2_D15") (class "Default")
      (node (ref "A2") (pin "33") (pinfunction "DB15_33") (pintype "passive"))
      (node (ref "U2") (pin "62") (pinfunction "PD15_62") (pintype "bidirectional"))
    )
    (net (code "42") (name "/ADC2_FRST") (class "Default")
      (node (ref "A2") (pin "15") (pinfunction "FRSTDATA_15") (pintype "passive"))
      (node (ref "U2") (pin "63") (pinfunction "PC6_63") (pintype "bidirectional"))
    )
    (net (code "43") (name "/ADC2_RD") (class "Default")
      (node (ref "A2") (pin "12") (pinfunction "RD#/SCLK_12") (pintype "passive"))
      (node (ref "U2") (pin "66") (pinfunction "PC9_66") (pintype "bidirectional"))
    )
    (net (code "44") (name "/ADC2_RST") (class "Default")
      (node (ref "A2") (pin "11") (pinfunction "RESET_11") (pintype "passive"))
      (node (ref "U2") (pin "67") (pinfunction "PA8_67") (pintype "bidirectional"))
    )
    (net (code "45") (name "/BOOT0") (class "Default")
      (node (ref "R14") (pin "2") (pinfunction "2_2") (pintype "passive"))
      (node (ref "U2") (pin "94") (pinfunction "BOOT0_94") (pintype "input"))
    )
    (net (code "46") (name "/ENB1_1") (class "Default")
      (node (ref "ASW1") (pin "1") (pinfunction "IN_1") (pintype "passive"))
      (node (ref "U2") (pin "96") (pinfunction "PB9_96") (pintype "bidirectional"))
    )
    (net (code "47") (name "/ENB1_2") (class "Default")
      (node (ref "ASW2") (pin "1") (pinfunction "IN_1") (pintype "passive"))
      (node (ref "U2") (pin "95") (pinfunction "PB8_95") (pintype "bidirectional"))
    )
    (net (code "48") (name "/ENB1_3") (class "Default")
      (node (ref "ASW3") (pin "1") (pinfunction "IN_1") (pintype "passive"))
      (node (ref "U2") (pin "93") (pinfunction "PB7_93") (pintype "bidirectional"))
    )
    (net (code "49") (name "/ENB1_4") (class "Default")
      (node (ref "ASW4") (pin "1") (pinfunction "IN_1") (pintype "passive"))
      (node (ref "U2") (pin "92") (pinfunction "PB6_92") (pintype "bidirectional"))
    )
    (net (code "50") (name "/ENB1_5") (class "Default")
      (node (ref "ASW5") (pin "1") (pinfunction "IN_1") (pintype "passive"))
      (node (ref "U2") (pin "91") (pinfunction "PB5_91") (pintype "bidirectional"))
    )
    (net (code "51") (name "/ENB1_6") (class "Default")
      (node (ref "ASW6") (pin "1") (pinfunction "IN_1") (pintype "passive"))
      (node (ref "U2") (pin "90") (pinfunction "PB4_90") (pintype "bidirectional"))
    )
    (net (code "52") (name "/ENB1_7") (class "Default")
      (node (ref "ASW7") (pin "1") (pinfunction "IN_1") (pintype "passive"))
      (node (ref "U2") (pin "89") (pinfunction "PB3_89") (pintype "bidirectional"))
    )
    (net (code "53") (name "/ENB1_8") (class "Default")
      (node (ref "ASW8") (pin "1") (pinfunction "IN_1") (pintype "passive"))
      (node (ref "U2") (pin "80") (pinfunction "PC12_80") (pintype "bidirectional"))
    )
    (net (code "54") (name "/ENB2_1") (class "Default")
      (node (ref "ASW9") (pin "1") (pinfunction "IN_1") (pintype "passive"))
      (node (ref "U2") (pin "29") (pinfunction "PA4_29") (pintype "bidirectional"))
    )
    (net (code "55") (name "/ENB2_2") (class "Default")
      (node (ref "ASW10") (pin "1") (pinfunction "IN_1") (pintype "passive"))
      (node (ref "U2") (pin "26") (pinfunction "PA3_26") (pintype "bidirectional"))
    )
    (net (code "56") (name "/ENB2_3") (class "Default")
      (node (ref "ASW11") (pin "1") (pinfunction "IN_1") (pintype "passive"))
      (node (ref "U2") (pin "25") (pinfunction "PA2_25") (pintype "bidirectional"))
    )
    (net (code "57") (name "/ENB2_4") (class "Default")
      (node (ref "ASW12") (pin "1") (pinfunction "IN_1") (pintype "passive"))
      (node (ref "U2") (pin "24") (pinfunction "PA1_24") (pintype "bidirectional"))
    )
    (net (code "58") (name "/ENB2_5") (class "Default")
      (node (ref "ASW13") (pin "1") (pinfunction "IN_1") (pintype "passive"))
      (node (ref "U2") (pin "18") (pinfunction "PC3_18") (pintype "bidirectional"))
    )
    (net (code "59") (name "/ENB2_6") (class "Default")
      (node (ref "ASW14") (pin "1") (pinfunction "IN_1") (pintype "passive"))
      (node (ref "U2") (pin "17") (pinfunction "PC2_17") (pintype "bidirectional"))
    )
    (net (code "60") (name "/ENB2_7") (class "Default")
      (node (ref "ASW15") (pin "1") (pinfunction "IN_1") (pintype "passive"))
      (node (ref "U2") (pin "16") (pinfunction "PC1_16") (pintype "bidirectional"))
    )
    (net (code "61") (name "/ENB2_8") (class "Default")
      (node (ref "ASW16") (pin "1") (pinfunction "IN_1") (pintype "passive"))
      (node (ref "U2") (pin "15") (pinfunction "PC0_15") (pintype "bidirectional"))
    )
    (net (code "62") (name "/ESP_RXD") (class "Default")
      (node (ref "*1") (pin "19") (pinfunction "GPIO1_19") (pintype "passive"))
      (node (ref "U2") (pin "69") (pinfunction "PA10_69") (pintype "bidirectional"))
    )
    (net (code "63") (name "/ESP_TXD") (class "Default")
      (node (ref "*1") (pin "20") (pinfunction "GPIO2_20") (pintype "passive"))
      (node (ref "U2") (pin "68") (pinfunction "PA9_68") (pintype "bidirectional"))
    )
    (net (code "64") (name "/Is_nework") (class "Default")
      (node (ref "U2") (pin "52") (pinfunction "PB13_52") (pintype "bidirectional"))
    )
    (net (code "65") (name "/KEY") (class "Default")
      (node (ref "C22") (pin "2") (pinfunction "2_2") (pintype "passive"))
      (node (ref "R11") (pin "1") (pinfunction "1_1") (pintype "passive"))
      (node (ref "S2") (pin "1") (pinfunction "1_1") (pintype "passive"))
      (node (ref "U2") (pin "23") (pinfunction "PA0-WKUP_23") (pintype "bidirectional"))
    )
    (net (code "66") (name "/OS1_0") (class "Default")
      (node (ref "A1") (pin "3") (pinfunction "OS0_3") (pintype "passive"))
      (node (ref "OS2") (pin "1") (pinfunction "1_1") (pintype "passive"))
    )
    (net (code "67") (name "/OS1_1") (class "Default")
      (node (ref "A1") (pin "4") (pinfunction "OS1_4") (pintype "passive"))
      (node (ref "OS5") (pin "1") (pinfunction "1_1") (pintype "passive"))
    )
    (net (code "68") (name "/OS1_2") (class "Default")
      (node (ref "A1") (pin "5") (pinfunction "OS2_5") (pintype "passive"))
      (node (ref "OS3") (pin "1") (pinfunction "1_1") (pintype "passive"))
    )
    (net (code "69") (name "/OS2_0") (class "Default")
      (node (ref "A2") (pin "3") (pinfunction "OS0_3") (pintype "passive"))
      (node (ref "OS7") (pin "1") (pinfunction "1_1") (pintype "passive"))
    )
    (net (code "70") (name "/OS2_1") (class "Default")
      (node (ref "A2") (pin "4") (pinfunction "OS1_4") (pintype "passive"))
      (node (ref "OS10") (pin "1") (pinfunction "1_1") (pintype "passive"))
    )
    (net (code "71") (name "/OS2_2") (class "Default")
      (node (ref "A2") (pin "5") (pinfunction "OS2_5") (pintype "passive"))
      (node (ref "OS8") (pin "1") (pinfunction "1_1") (pintype "passive"))
    )
    (net (code "72") (name "/O_DOWN") (class "Default")
      (node (ref "C21") (pin "2") (pinfunction "2_2") (pintype "passive"))
      (node (ref "R9") (pin "1") (pinfunction "1_1") (pintype "passive"))
      (node (ref "S1") (pin "1") (pinfunction "1_1") (pintype "passive"))
      (node (ref "U2") (pin "48") (pinfunction "PB11_48") (pintype "bidirectional"))
    )
    (net (code "73") (name "/RESET") (class "Default")
      (node (ref "C20") (pin "2") (pinfunction "2_2") (pintype "passive"))
      (node (ref "R10") (pin "1") (pinfunction "1_1") (pintype "passive"))
      (node (ref "U2") (pin "14") (pinfunction "NRST_14") (pintype "bidirectional"))
    )
    (net (code "74") (name "/STBY1") (class "Default")
      (node (ref "A1") (pin "7") (pinfunction "STBY#_7") (pintype "passive"))
      (node (ref "OS4") (pin "1") (pinfunction "1_1") (pintype "passive"))
    )
    (net (code "75") (name "/STBY2") (class "Default")
      (node (ref "A2") (pin "7") (pinfunction "STBY#_7") (pintype "passive"))
      (node (ref "OS9") (pin "1") (pinfunction "1_1") (pintype "passive"))
    )
    (net (code "76") (name "/SWCLK") (class "Default")
      (node (ref "J1") (pin "2") (pinfunction "2_2") (pintype "passive"))
      (node (ref "U2") (pin "76") (pinfunction "PA14_76") (pintype "bidirectional"))
    )
    (net (code "77") (name "/SWDIO") (class "Default")
      (node (ref "J1") (pin "3") (pinfunction "3_3") (pintype "passive"))
      (node (ref "U2") (pin "72") (pinfunction "PA13_72") (pintype "bidirectional"))
    )
    (net (code "78") (name "/TEM") (class "Default")
      (node (ref "P2") (pin "2") (pinfunction "2_2") (pintype "passive"))
      (node (ref "U2") (pin "53") (pinfunction "PB14_53") (pintype "bidirectional"))
    )
    (net (code "79") (name "/Ve") (class "Default")
      (node (ref "ASW1") (pin "4") (pinfunction "NC_4") (pintype "passive"))
      (node (ref "ASW10") (pin "4") (pinfunction "NC_4") (pintype "passive"))
      (node (ref "ASW11") (pin "4") (pinfunction "NC_4") (pintype "passive"))
      (node (ref "ASW12") (pin "4") (pinfunction "NC_4") (pintype "passive"))
      (node (ref "ASW13") (pin "4") (pinfunction "NC_4") (pintype "passive"))
      (node (ref "ASW14") (pin "4") (pinfunction "NC_4") (pintype "passive"))
      (node (ref "ASW15") (pin "4") (pinfunction "NC_4") (pintype "passive"))
      (node (ref "ASW16") (pin "4") (pinfunction "NC_4") (pintype "passive"))
      (node (ref "ASW2") (pin "4") (pinfunction "NC_4") (pintype "passive"))
      (node (ref "ASW3") (pin "4") (pinfunction "NC_4") (pintype "passive"))
      (node (ref "ASW4") (pin "4") (pinfunction "NC_4") (pintype "passive"))
      (node (ref "ASW5") (pin "4") (pinfunction "NC_4") (pintype "passive"))
      (node (ref "ASW6") (pin "4") (pinfunction "NC_4") (pintype "passive"))
      (node (ref "ASW7") (pin "4") (pinfunction "NC_4") (pintype "passive"))
      (node (ref "ASW8") (pin "4") (pinfunction "NC_4") (pintype "passive"))
      (node (ref "ASW9") (pin "4") (pinfunction "NC_4") (pintype "passive"))
      (node (ref "D1") (pin "10") (pinfunction "+INC_10") (pintype "passive"))
      (node (ref "D1") (pin "12") (pinfunction "+IND_12") (pintype "passive"))
      (node (ref "D1") (pin "3") (pinfunction "+INA_3") (pintype "passive"))
      (node (ref "D1") (pin "5") (pinfunction "+INB_5") (pintype "passive"))
      (node (ref "D2") (pin "10") (pinfunction "+INC_10") (pintype "passive"))
      (node (ref "D2") (pin "12") (pinfunction "+IND_12") (pintype "passive"))
      (node (ref "D2") (pin "3") (pinfunction "+INA_3") (pintype "passive"))
      (node (ref "D2") (pin "5") (pinfunction "+INB_5") (pintype "passive"))
      (node (ref "D3") (pin "10") (pinfunction "+INC_10") (pintype "passive"))
      (node (ref "D3") (pin "12") (pinfunction "+IND_12") (pintype "passive"))
      (node (ref "D3") (pin "3") (pinfunction "+INA_3") (pintype "passive"))
      (node (ref "D3") (pin "5") (pinfunction "+INB_5") (pintype "passive"))
      (node (ref "D4") (pin "10") (pinfunction "+INC_10") (pintype "passive"))
      (node (ref "D4") (pin "12") (pinfunction "+IND_12") (pintype "passive"))
      (node (ref "D4") (pin "3") (pinfunction "+INA_3") (pintype "passive"))
      (node (ref "D4") (pin "5") (pinfunction "+INB_5") (pintype "passive"))
      (node (ref "R5") (pin "2") (pinfunction "2_2") (pintype "passive"))
      (node (ref "U1") (pin "1") (pinfunction "OUT_1") (pintype "passive"))
    )
    (net (code "80") (name "/Vrefin") (class "Default")
      (node (ref "R4") (pin "1") (pinfunction "1_1") (pintype "passive"))
      (node (ref "R7") (pin "1") (pinfunction "1_1") (pintype "passive"))
      (node (ref "U1") (pin "3") (pinfunction "+IN_3") (pintype "passive"))
    )
    (net (code "81") (name "/j1_1") (class "Default")
      (node (ref "D1") (pin "2") (pinfunction "-INA_2") (pintype "passive"))
      (node (ref "P4") (pin "1") (pinfunction "1_1") (pintype "passive"))
      (node (ref "R18") (pin "1") (pinfunction "1_1") (pintype "passive"))
    )
    (net (code "82") (name "/j1_2") (class "Default")
      (node (ref "D1") (pin "6") (pinfunction "-INB_6") (pintype "passive"))
      (node (ref "P4") (pin "2") (pinfunction "2_2") (pintype "passive"))
      (node (ref "R19") (pin "1") (pinfunction "1_1") (pintype "passive"))
    )
    (net (code "83") (name "/j1_3") (class "Default")
      (node (ref "D1") (pin "9") (pinfunction "-INC_9") (pintype "passive"))
      (node (ref "P4") (pin "3") (pinfunction "3_3") (pintype "passive"))
      (node (ref "R20") (pin "1") (pinfunction "1_1") (pintype "passive"))
    )
    (net (code "84") (name "/j1_4") (class "Default")
      (node (ref "D1") (pin "13") (pinfunction "-IND_13") (pintype "passive"))
      (node (ref "P4") (pin "4") (pinfunction "4_4") (pintype "passive"))
      (node (ref "R21") (pin "1") (pinfunction "1_1") (pintype "passive"))
    )
    (net (code "85") (name "/j1_5") (class "Default")
      (node (ref "D2") (pin "2") (pinfunction "-INA_2") (pintype "passive"))
      (node (ref "P4") (pin "5") (pinfunction "5_5") (pintype "passive"))
      (node (ref "R22") (pin "1") (pinfunction "1_1") (pintype "passive"))
    )
    (net (code "86") (name "/j1_6") (class "Default")
      (node (ref "D2") (pin "6") (pinfunction "-INB_6") (pintype "passive"))
      (node (ref "P4") (pin "6") (pinfunction "6_6") (pintype "passive"))
      (node (ref "R23") (pin "1") (pinfunction "1_1") (pintype "passive"))
    )
    (net (code "87") (name "/j1_7") (class "Default")
      (node (ref "D2") (pin "9") (pinfunction "-INC_9") (pintype "passive"))
      (node (ref "P4") (pin "7") (pinfunction "7_7") (pintype "passive"))
      (node (ref "R24") (pin "1") (pinfunction "1_1") (pintype "passive"))
    )
    (net (code "88") (name "/j1_8") (class "Default")
      (node (ref "D2") (pin "13") (pinfunction "-IND_13") (pintype "passive"))
      (node (ref "P4") (pin "8") (pinfunction "8_8") (pintype "passive"))
      (node (ref "R25") (pin "1") (pinfunction "1_1") (pintype "passive"))
    )
    (net (code "89") (name "/j2_1") (class "Default")
      (node (ref "D3") (pin "2") (pinfunction "-INA_2") (pintype "passive"))
      (node (ref "P4") (pin "9") (pinfunction "9_9") (pintype "passive"))
      (node (ref "R26") (pin "1") (pinfunction "1_1") (pintype "passive"))
    )
    (net (code "90") (name "/j2_2") (class "Default")
      (node (ref "D3") (pin "6") (pinfunction "-INB_6") (pintype "passive"))
      (node (ref "P4") (pin "10") (pinfunction "10_10") (pintype "passive"))
      (node (ref "R27") (pin "1") (pinfunction "1_1") (pintype "passive"))
    )
    (net (code "91") (name "/j2_3") (class "Default")
      (node (ref "D3") (pin "9") (pinfunction "-INC_9") (pintype "passive"))
      (node (ref "P4") (pin "11") (pinfunction "11_11") (pintype "passive"))
      (node (ref "R28") (pin "1") (pinfunction "1_1") (pintype "passive"))
    )
    (net (code "92") (name "/j2_4") (class "Default")
      (node (ref "D3") (pin "13") (pinfunction "-IND_13") (pintype "passive"))
      (node (ref "P4") (pin "12") (pinfunction "12_12") (pintype "passive"))
      (node (ref "R29") (pin "1") (pinfunction "1_1") (pintype "passive"))
    )
    (net (code "93") (name "/j2_5") (class "Default")
      (node (ref "D4") (pin "2") (pinfunction "-INA_2") (pintype "passive"))
      (node (ref "P4") (pin "13") (pinfunction "13_13") (pintype "passive"))
      (node (ref "R30") (pin "1") (pinfunction "1_1") (pintype "passive"))
    )
    (net (code "94") (name "/j2_6") (class "Default")
      (node (ref "D4") (pin "6") (pinfunction "-INB_6") (pintype "passive"))
      (node (ref "P4") (pin "14") (pinfunction "14_14") (pintype "passive"))
      (node (ref "R31") (pin "1") (pinfunction "1_1") (pintype "passive"))
    )
    (net (code "95") (name "/j2_7") (class "Default")
      (node (ref "D4") (pin "9") (pinfunction "-INC_9") (pintype "passive"))
      (node (ref "P4") (pin "15") (pinfunction "15_15") (pintype "passive"))
      (node (ref "R32") (pin "1") (pinfunction "1_1") (pintype "passive"))
    )
    (net (code "96") (name "/j2_8") (class "Default")
      (node (ref "D4") (pin "13") (pinfunction "-IND_13") (pintype "passive"))
      (node (ref "P4") (pin "16") (pinfunction "16_16") (pintype "passive"))
      (node (ref "R33") (pin "1") (pinfunction "1_1") (pintype "passive"))
    )
    (net (code "97") (name "/out1_1") (class "Default")
      (node (ref "A1") (pin "49") (pinfunction "V1_49") (pintype "passive"))
      (node (ref "D1") (pin "1") (pinfunction "OUTA_1") (pintype "passive"))
      (node (ref "R18") (pin "2") (pinfunction "2_2") (pintype "passive"))
    )
    (net (code "98") (name "/out1_2") (class "Default")
      (node (ref "A1") (pin "51") (pinfunction "V2_51") (pintype "passive"))
      (node (ref "D1") (pin "7") (pinfunction "OUTB_7") (pintype "passive"))
      (node (ref "R19") (pin "2") (pinfunction "2_2") (pintype "passive"))
    )
    (net (code "99") (name "/out1_3") (class "Default")
      (node (ref "A1") (pin "53") (pinfunction "V3_53") (pintype "passive"))
      (node (ref "D1") (pin "8") (pinfunction "OUTC_8") (pintype "passive"))
      (node (ref "R20") (pin "2") (pinfunction "2_2") (pintype "passive"))
    )
    (net (code "100") (name "/out1_4") (class "Default")
      (node (ref "A1") (pin "55") (pinfunction "V4_55") (pintype "passive"))
      (node (ref "D1") (pin "14") (pinfunction "OUTD_14") (pintype "passive"))
      (node (ref "R21") (pin "2") (pinfunction "2_2") (pintype "passive"))
    )
    (net (code "101") (name "/out1_5") (class "Default")
      (node (ref "A1") (pin "57") (pinfunction "V5_57") (pintype "passive"))
      (node (ref "D2") (pin "1") (pinfunction "OUTA_1") (pintype "passive"))
      (node (ref "R22") (pin "2") (pinfunction "2_2") (pintype "passive"))
    )
    (net (code "102") (name "/out1_6") (class "Default")
      (node (ref "A1") (pin "59") (pinfunction "V6_59") (pintype "passive"))
      (node (ref "D2") (pin "7") (pinfunction "OUTB_7") (pintype "passive"))
      (node (ref "R23") (pin "2") (pinfunction "2_2") (pintype "passive"))
    )
    (net (code "103") (name "/out1_7") (class "Default")
      (node (ref "A1") (pin "61") (pinfunction "V7_61") (pintype "passive"))
      (node (ref "D2") (pin "8") (pinfunction "OUTC_8") (pintype "passive"))
      (node (ref "R24") (pin "2") (pinfunction "2_2") (pintype "passive"))
    )
    (net (code "104") (name "/out1_8") (class "Default")
      (node (ref "A1") (pin "63") (pinfunction "V8_63") (pintype "passive"))
      (node (ref "D2") (pin "14") (pinfunction "OUTD_14") (pintype "passive"))
      (node (ref "R25") (pin "2") (pinfunction "2_2") (pintype "passive"))
    )
    (net (code "105") (name "/out2_1") (class "Default")
      (node (ref "A2") (pin "49") (pinfunction "V1_49") (pintype "passive"))
      (node (ref "D3") (pin "1") (pinfunction "OUTA_1") (pintype "passive"))
      (node (ref "R26") (pin "2") (pinfunction "2_2") (pintype "passive"))
    )
    (net (code "106") (name "/out2_2") (class "Default")
      (node (ref "A2") (pin "51") (pinfunction "V2_51") (pintype "passive"))
      (node (ref "D3") (pin "7") (pinfunction "OUTB_7") (pintype "passive"))
      (node (ref "R27") (pin "2") (pinfunction "2_2") (pintype "passive"))
    )
    (net (code "107") (name "/out2_3") (class "Default")
      (node (ref "A2") (pin "53") (pinfunction "V3_53") (pintype "passive"))
      (node (ref "D3") (pin "8") (pinfunction "OUTC_8") (pintype "passive"))
      (node (ref "R28") (pin "2") (pinfunction "2_2") (pintype "passive"))
    )
    (net (code "108") (name "/out2_4") (class "Default")
      (node (ref "A2") (pin "55") (pinfunction "V4_55") (pintype "passive"))
      (node (ref "D3") (pin "14") (pinfunction "OUTD_14") (pintype "passive"))
      (node (ref "R29") (pin "2") (pinfunction "2_2") (pintype "passive"))
    )
    (net (code "109") (name "/out2_5") (class "Default")
      (node (ref "A2") (pin "57") (pinfunction "V5_57") (pintype "passive"))
      (node (ref "D4") (pin "1") (pinfunction "OUTA_1") (pintype "passive"))
      (node (ref "R30") (pin "2") (pinfunction "2_2") (pintype "passive"))
    )
    (net (code "110") (name "/out2_6") (class "Default")
      (node (ref "A2") (pin "59") (pinfunction "V6_59") (pintype "passive"))
      (node (ref "D4") (pin "7") (pinfunction "OUTB_7") (pintype "passive"))
      (node (ref "R31") (pin "2") (pinfunction "2_2") (pintype "passive"))
    )
    (net (code "111") (name "/out2_7") (class "Default")
      (node (ref "A2") (pin "61") (pinfunction "V7_61") (pintype "passive"))
      (node (ref "D4") (pin "8") (pinfunction "OUTC_8") (pintype "passive"))
      (node (ref "R32") (pin "2") (pinfunction "2_2") (pintype "passive"))
    )
    (net (code "112") (name "/out2_8") (class "Default")
      (node (ref "A2") (pin "63") (pinfunction "V8_63") (pintype "passive"))
      (node (ref "D4") (pin "14") (pinfunction "OUTD_14") (pintype "passive"))
      (node (ref "R33") (pin "2") (pinfunction "2_2") (pintype "passive"))
    )
    (net (code "113") (name "/r1_1") (class "Default")
      (node (ref "ASW1") (pin "5") (pinfunction "COM_5") (pintype "passive"))
      (node (ref "P3") (pin "1") (pinfunction "1_1") (pintype "passive"))
    )
    (net (code "114") (name "/r1_2") (class "Default")
      (node (ref "ASW2") (pin "5") (pinfunction "COM_5") (pintype "passive"))
      (node (ref "P3") (pin "2") (pinfunction "2_2") (pintype "passive"))
    )
    (net (code "115") (name "/r1_3") (class "Default")
      (node (ref "ASW3") (pin "5") (pinfunction "COM_5") (pintype "passive"))
      (node (ref "P3") (pin "3") (pinfunction "3_3") (pintype "passive"))
    )
    (net (code "116") (name "/r1_4") (class "Default")
      (node (ref "ASW4") (pin "5") (pinfunction "COM_5") (pintype "passive"))
      (node (ref "P3") (pin "4") (pinfunction "4_4") (pintype "passive"))
    )
    (net (code "117") (name "/r1_5") (class "Default")
      (node (ref "ASW5") (pin "5") (pinfunction "COM_5") (pintype "passive"))
      (node (ref "P3") (pin "5") (pinfunction "5_5") (pintype "passive"))
    )
    (net (code "118") (name "/r1_6") (class "Default")
      (node (ref "ASW6") (pin "5") (pinfunction "COM_5") (pintype "passive"))
      (node (ref "P3") (pin "6") (pinfunction "6_6") (pintype "passive"))
    )
    (net (code "119") (name "/r1_7") (class "Default")
      (node (ref "ASW7") (pin "5") (pinfunction "COM_5") (pintype "passive"))
      (node (ref "P3") (pin "7") (pinfunction "7_7") (pintype "passive"))
    )
    (net (code "120") (name "/r1_8") (class "Default")
      (node (ref "ASW8") (pin "5") (pinfunction "COM_5") (pintype "passive"))
      (node (ref "P3") (pin "8") (pinfunction "8_8") (pintype "passive"))
    )
    (net (code "121") (name "/r2_1") (class "Default")
      (node (ref "ASW9") (pin "5") (pinfunction "COM_5") (pintype "passive"))
      (node (ref "P3") (pin "9") (pinfunction "9_9") (pintype "passive"))
    )
    (net (code "122") (name "/r2_2") (class "Default")
      (node (ref "ASW10") (pin "5") (pinfunction "COM_5") (pintype "passive"))
      (node (ref "P3") (pin "10") (pinfunction "10_10") (pintype "passive"))
    )
    (net (code "123") (name "/r2_3") (class "Default")
      (node (ref "ASW11") (pin "5") (pinfunction "COM_5") (pintype "passive"))
      (node (ref "P3") (pin "11") (pinfunction "11_11") (pintype "passive"))
    )
    (net (code "124") (name "/r2_4") (class "Default")
      (node (ref "ASW12") (pin "5") (pinfunction "COM_5") (pintype "passive"))
      (node (ref "P3") (pin "12") (pinfunction "12_12") (pintype "passive"))
    )
    (net (code "125") (name "/r2_5") (class "Default")
      (node (ref "ASW13") (pin "5") (pinfunction "COM_5") (pintype "passive"))
      (node (ref "P3") (pin "13") (pinfunction "13_13") (pintype "passive"))
    )
    (net (code "126") (name "/r2_6") (class "Default")
      (node (ref "ASW14") (pin "5") (pinfunction "COM_5") (pintype "passive"))
      (node (ref "P3") (pin "14") (pinfunction "14_14") (pintype "passive"))
    )
    (net (code "127") (name "/r2_7") (class "Default")
      (node (ref "ASW15") (pin "5") (pinfunction "COM_5") (pintype "passive"))
      (node (ref "P3") (pin "15") (pinfunction "15_15") (pintype "passive"))
    )
    (net (code "128") (name "/r2_8") (class "Default")
      (node (ref "ASW16") (pin "5") (pinfunction "COM_5") (pintype "passive"))
      (node (ref "P3") (pin "16") (pinfunction "16_16") (pintype "passive"))
    )
    (net (code "129") (name "AGND") (class "Default")
      (node (ref "A1") (pin "2") (pinfunction "AGND_2") (pintype "passive"))
      (node (ref "A1") (pin "26") (pinfunction "AGND_26") (pintype "passive"))
      (node (ref "A1") (pin "35") (pinfunction "AGND_35") (pintype "passive"))
      (node (ref "A1") (pin "40") (pinfunction "AGND_40") (pintype "passive"))
      (node (ref "A1") (pin "41") (pinfunction "AGND_41") (pintype "passive"))
      (node (ref "A1") (pin "43") (pinfunction "REFGND_43") (pintype "passive"))
      (node (ref "A1") (pin "46") (pinfunction "REFGND_46") (pintype "passive"))
      (node (ref "A1") (pin "47") (pinfunction "AGND_47") (pintype "passive"))
      (node (ref "A1") (pin "50") (pinfunction "V1GND_50") (pintype "passive"))
      (node (ref "A1") (pin "52") (pinfunction "V2GND_52") (pintype "passive"))
      (node (ref "A1") (pin "54") (pinfunction "V3GND_54") (pintype "passive"))
      (node (ref "A1") (pin "56") (pinfunction "V4GND_56") (pintype "passive"))
      (node (ref "A1") (pin "58") (pinfunction "V5GND_58") (pintype "passive"))
      (node (ref "A1") (pin "6") (pinfunction "PAR#/SER/BYTE_SEL_6") (pintype "passive"))
      (node (ref "A1") (pin "60") (pinfunction "V6GND_60") (pintype "passive"))
      (node (ref "A1") (pin "62") (pinfunction "V7GND_62") (pintype "passive"))
      (node (ref "A1") (pin "64") (pinfunction "V8GND_64") (pintype "passive"))
      (node (ref "A2") (pin "2") (pinfunction "AGND_2") (pintype "passive"))
      (node (ref "A2") (pin "26") (pinfunction "AGND_26") (pintype "passive"))
      (node (ref "A2") (pin "35") (pinfunction "AGND_35") (pintype "passive"))
      (node (ref "A2") (pin "40") (pinfunction "AGND_40") (pintype "passive"))
      (node (ref "A2") (pin "41") (pinfunction "AGND_41") (pintype "passive"))
      (node (ref "A2") (pin "43") (pinfunction "REFGND_43") (pintype "passive"))
      (node (ref "A2") (pin "46") (pinfunction "REFGND_46") (pintype "passive"))
      (node (ref "A2") (pin "47") (pinfunction "AGND_47") (pintype "passive"))
      (node (ref "A2") (pin "50") (pinfunction "V1GND_50") (pintype "passive"))
      (node (ref "A2") (pin "52") (pinfunction "V2GND_52") (pintype "passive"))
      (node (ref "A2") (pin "54") (pinfunction "V3GND_54") (pintype "passive"))
      (node (ref "A2") (pin "56") (pinfunction "V4GND_56") (pintype "passive"))
      (node (ref "A2") (pin "58") (pinfunction "V5GND_58") (pintype "passive"))
      (node (ref "A2") (pin "6") (pinfunction "PAR#/SER/BYTE_SEL_6") (pintype "passive"))
      (node (ref "A2") (pin "60") (pinfunction "V6GND_60") (pintype "passive"))
      (node (ref "A2") (pin "62") (pinfunction "V7GND_62") (pintype "passive"))
      (node (ref "A2") (pin "64") (pinfunction "V8GND_64") (pintype "passive"))
      (node (ref "ASW1") (pin "3") (pinfunction "GND_3") (pintype "passive"))
      (node (ref "ASW1") (pin "6") (pinfunction "NO_6") (pintype "passive"))
      (node (ref "ASW10") (pin "3") (pinfunction "GND_3") (pintype "passive"))
      (node (ref "ASW10") (pin "6") (pinfunction "NO_6") (pintype "passive"))
      (node (ref "ASW11") (pin "3") (pinfunction "GND_3") (pintype "passive"))
      (node (ref "ASW11") (pin "6") (pinfunction "NO_6") (pintype "passive"))
      (node (ref "ASW12") (pin "3") (pinfunction "GND_3") (pintype "passive"))
      (node (ref "ASW12") (pin "6") (pinfunction "NO_6") (pintype "passive"))
      (node (ref "ASW13") (pin "3") (pinfunction "GND_3") (pintype "passive"))
      (node (ref "ASW13") (pin "6") (pinfunction "NO_6") (pintype "passive"))
      (node (ref "ASW14") (pin "3") (pinfunction "GND_3") (pintype "passive"))
      (node (ref "ASW14") (pin "6") (pinfunction "NO_6") (pintype "passive"))
      (node (ref "ASW15") (pin "3") (pinfunction "GND_3") (pintype "passive"))
      (node (ref "ASW15") (pin "6") (pinfunction "NO_6") (pintype "passive"))
      (node (ref "ASW16") (pin "3") (pinfunction "GND_3") (pintype "passive"))
      (node (ref "ASW16") (pin "6") (pinfunction "NO_6") (pintype "passive"))
      (node (ref "ASW2") (pin "3") (pinfunction "GND_3") (pintype "passive"))
      (node (ref "ASW2") (pin "6") (pinfunction "NO_6") (pintype "passive"))
      (node (ref "ASW3") (pin "3") (pinfunction "GND_3") (pintype "passive"))
      (node (ref "ASW3") (pin "6") (pinfunction "NO_6") (pintype "passive"))
      (node (ref "ASW4") (pin "3") (pinfunction "GND_3") (pintype "passive"))
      (node (ref "ASW4") (pin "6") (pinfunction "NO_6") (pintype "passive"))
      (node (ref "ASW5") (pin "3") (pinfunction "GND_3") (pintype "passive"))
      (node (ref "ASW5") (pin "6") (pinfunction "NO_6") (pintype "passive"))
      (node (ref "ASW6") (pin "3") (pinfunction "GND_3") (pintype "passive"))
      (node (ref "ASW6") (pin "6") (pinfunction "NO_6") (pintype "passive"))
      (node (ref "ASW7") (pin "3") (pinfunction "GND_3") (pintype "passive"))
      (node (ref "ASW7") (pin "6") (pinfunction "NO_6") (pintype "passive"))
      (node (ref "ASW8") (pin "3") (pinfunction "GND_3") (pintype "passive"))
      (node (ref "ASW8") (pin "6") (pinfunction "NO_6") (pintype "passive"))
      (node (ref "ASW9") (pin "3") (pinfunction "GND_3") (pintype "passive"))
      (node (ref "ASW9") (pin "6") (pinfunction "NO_6") (pintype "passive"))
      (node (ref "C10") (pin "1") (pinfunction "1_1") (pintype "passive"))
      (node (ref "C15") (pin "2") (pinfunction "2_2") (pintype "passive"))
      (node (ref "C16") (pin "1") (pinfunction "1_1") (pintype "passive"))
      (node (ref "C17") (pin "1") (pinfunction "1_1") (pintype "passive"))
      (node (ref "C18") (pin "1") (pinfunction "1_1") (pintype "passive"))
      (node (ref "C19") (pin "1") (pinfunction "1_1") (pintype "passive"))
      (node (ref "C23") (pin "2") (pinfunction "2_2") (pintype "passive"))
      (node (ref "C24") (pin "2") (pinfunction "2_2") (pintype "passive"))
      (node (ref "C25") (pin "2") (pinfunction "2_2") (pintype "passive"))
      (node (ref "C32") (pin "2") (pinfunction "2_2") (pintype "passive"))
      (node (ref "C33") (pin "2") (pinfunction "2_2") (pintype "passive"))
      (node (ref "C34") (pin "2") (pinfunction "2_2") (pintype "passive"))
      (node (ref "C35") (pin "1") (pinfunction "1_1") (pintype "passive"))
      (node (ref "C36") (pin "1") (pinfunction "1_1") (pintype "passive"))
      (node (ref "C37") (pin "1") (pinfunction "1_1") (pintype "passive"))
      (node (ref "C38") (pin "1") (pinfunction "1_1") (pintype "passive"))
      (node (ref "C39") (pin "2") (pinfunction "2_2") (pintype "passive"))
      (node (ref "C40") (pin "2") (pinfunction "2_2") (pintype "passive"))
      (node (ref "C41") (pin "2") (pinfunction "2_2") (pintype "passive"))
      (node (ref "C42") (pin "2") (pinfunction "2_2") (pintype "passive"))
      (node (ref "C43") (pin "2") (pinfunction "2_2") (pintype "passive"))
      (node (ref "C7") (pin "1") (pinfunction "1_1") (pintype "passive"))
      (node (ref "C8") (pin "1") (pinfunction "1_1") (pintype "passive"))
      (node (ref "C9") (pin "1") (pinfunction "1_1") (pintype "passive"))
      (node (ref "D1") (pin "11") (pinfunction "V-_11") (pintype "passive"))
      (node (ref "D2") (pin "11") (pinfunction "V-_11") (pintype "passive"))
      (node (ref "D3") (pin "11") (pinfunction "V-_11") (pintype "passive"))
      (node (ref "D4") (pin "11") (pinfunction "V-_11") (pintype "passive"))
      (node (ref "D5") (pin "K") (pinfunction "K_K") (pintype "passive"))
      (node (ref "D6") (pin "1") (pinfunction "A_1") (pintype "passive"))
      (node (ref "OS1") (pin "2") (pinfunction "2_2") (pintype "passive"))
      (node (ref "OS10") (pin "2") (pinfunction "2_2") (pintype "passive"))
      (node (ref "OS5") (pin "2") (pinfunction "2_2") (pintype "passive"))
      (node (ref "OS6") (pin "2") (pinfunction "2_2") (pintype "passive"))
      (node (ref "R3") (pin "2") (pinfunction "2_2") (pintype "passive"))
      (node (ref "R7") (pin "2") (pinfunction "2_2") (pintype "passive"))
      (node (ref "U1") (pin "2") (pinfunction "V-_2") (pintype "passive"))
    )
    (net (code "130") (name "AVCC_5") (class "Default")
      (node (ref "A1") (pin "1") (pinfunction "AVcc_1") (pintype "passive"))
      (node (ref "A1") (pin "37") (pinfunction "AVcc_37") (pintype "passive"))
      (node (ref "A1") (pin "38") (pinfunction "AVcc_38") (pintype "passive"))
      (node (ref "A1") (pin "44") (pinfunction "REFCAPA_44") (pintype "passive"))
      (node (ref "A1") (pin "45") (pinfunction "REFCAPB_45") (pintype "passive"))
      (node (ref "A1") (pin "48") (pinfunction "AVcc_48") (pintype "passive"))
      (node (ref "A2") (pin "1") (pinfunction "AVcc_1") (pintype "passive"))
      (node (ref "A2") (pin "37") (pinfunction "AVcc_37") (pintype "passive"))
      (node (ref "A2") (pin "38") (pinfunction "AVcc_38") (pintype "passive"))
      (node (ref "A2") (pin "44") (pinfunction "REFCAPA_44") (pintype "passive"))
      (node (ref "A2") (pin "45") (pinfunction "REFCAPB_45") (pintype "passive"))
      (node (ref "A2") (pin "48") (pinfunction "AVcc_48") (pintype "passive"))
      (node (ref "ASW1") (pin "2") (pinfunction "V+_2") (pintype "passive"))
      (node (ref "ASW10") (pin "2") (pinfunction "V+_2") (pintype "passive"))
      (node (ref "ASW11") (pin "2") (pinfunction "V+_2") (pintype "passive"))
      (node (ref "ASW12") (pin "2") (pinfunction "V+_2") (pintype "passive"))
      (node (ref "ASW13") (pin "2") (pinfunction "V+_2") (pintype "passive"))
      (node (ref "ASW14") (pin "2") (pinfunction "V+_2") (pintype "passive"))
      (node (ref "ASW15") (pin "2") (pinfunction "V+_2") (pintype "passive"))
      (node (ref "ASW16") (pin "2") (pinfunction "V+_2") (pintype "passive"))
      (node (ref "ASW2") (pin "2") (pinfunction "V+_2") (pintype "passive"))
      (node (ref "ASW3") (pin "2") (pinfunction "V+_2") (pintype "passive"))
      (node (ref "ASW4") (pin "2") (pinfunction "V+_2") (pintype "passive"))
      (node (ref "ASW5") (pin "2") (pinfunction "V+_2") (pintype "passive"))
      (node (ref "ASW6") (pin "2") (pinfunction "V+_2") (pintype "passive"))
      (node (ref "ASW7") (pin "2") (pinfunction "V+_2") (pintype "passive"))
      (node (ref "ASW8") (pin "2") (pinfunction "V+_2") (pintype "passive"))
      (node (ref "ASW9") (pin "2") (pinfunction "V+_2") (pintype "passive"))
      (node (ref "C15") (pin "1") (pinfunction "1_1") (pintype "passive"))
      (node (ref "C16") (pin "2") (pinfunction "2_2") (pintype "passive"))
      (node (ref "C17") (pin "2") (pinfunction "2_2") (pintype "passive"))
      (node (ref "C18") (pin "2") (pinfunction "2_2") (pintype "passive"))
      (node (ref "C19") (pin "2") (pinfunction "2_2") (pintype "passive"))
      (node (ref "C23") (pin "1") (pinfunction "1_1") (pintype "passive"))
      (node (ref "C34") (pin "1") (pinfunction "1_1") (pintype "passive"))
      (node (ref "C35") (pin "2") (pinfunction "2_2") (pintype "passive"))
      (node (ref "C36") (pin "2") (pinfunction "2_2") (pintype "passive"))
      (node (ref "C37") (pin "2") (pinfunction "2_2") (pintype "passive"))
      (node (ref "C38") (pin "2") (pinfunction "2_2") (pintype "passive"))
      (node (ref "C39") (pin "1") (pinfunction "1_1") (pintype "passive"))
      (node (ref "C7") (pin "2") (pinfunction "2_2") (pintype "passive"))
      (node (ref "C8") (pin "2") (pinfunction "2_2") (pintype "passive"))
      (node (ref "C9") (pin "2") (pinfunction "2_2") (pintype "passive"))
      (node (ref "D1") (pin "4") (pinfunction "V+_4") (pintype "passive"))
      (node (ref "D2") (pin "4") (pinfunction "V+_4") (pintype "passive"))
      (node (ref "D3") (pin "4") (pinfunction "V+_4") (pintype "passive"))
      (node (ref "D4") (pin "4") (pinfunction "V+_4") (pintype "passive"))
      (node (ref "OS2") (pin "2") (pinfunction "2_2") (pintype "passive"))
      (node (ref "OS3") (pin "2") (pinfunction "2_2") (pintype "passive"))
      (node (ref "OS4") (pin "2") (pinfunction "2_2") (pintype "passive"))
      (node (ref "OS7") (pin "2") (pinfunction "2_2") (pintype "passive"))
      (node (ref "OS8") (pin "2") (pinfunction "2_2") (pintype "passive"))
      (node (ref "OS9") (pin "2") (pinfunction "2_2") (pintype "passive"))
      (node (ref "R1") (pin "2") (pinfunction "2_2") (pintype "passive"))
      (node (ref "R6") (pin "1") (pinfunction "1_1") (pintype "passive"))
      (node (ref "U1") (pin "5") (pinfunction "V+_5") (pintype "passive"))
      (node (ref "VR2") (pin "2") (pinfunction "Vout_2") (pintype "passive"))
    )
    (net (code "131") (name "GND") (class "Default")
      (node (ref "*1") (pin "1") (pinfunction "GND_1") (pintype "passive"))
      (node (ref "*1") (pin "11") (pinfunction "GND_11") (pintype "passive"))
      (node (ref "*1") (pin "12") (pinfunction "GND_12") (pintype "passive"))
      (node (ref "*1") (pin "13") (pinfunction "GND_13") (pintype "passive"))
      (node (ref "*1") (pin "16") (pinfunction "GND_16") (pintype "passive"))
      (node (ref "*1") (pin "17") (pinfunction "GND_17") (pintype "passive"))
      (node (ref "*1") (pin "28") (pinfunction "GND_28") (pintype "passive"))
      (node (ref "*1") (pin "29") (pinfunction "GND_29") (pintype "passive"))
      (node (ref "*1") (pin "44") (pinfunction "GND_44") (pintype "passive"))
      (node (ref "*1") (pin "8") (pinfunction "GND_8") (pintype "passive"))
      (node (ref "*1") (pin "9") (pinfunction "GND_9") (pintype "passive"))
      (node (ref "C1") (pin "1") (pinfunction "1_1") (pintype "passive"))
      (node (ref "C11") (pin "1") (pinfunction "1_1") (pintype "passive"))
      (node (ref "C12") (pin "1") (pinfunction "1_1") (pintype "passive"))
      (node (ref "C13") (pin "1") (pinfunction "1_1") (pintype "passive"))
      (node (ref "C14") (pin "1") (pinfunction "1_1") (pintype "passive"))
      (node (ref "C2") (pin "1") (pinfunction "1_1") (pintype "passive"))
      (node (ref "C20") (pin "1") (pinfunction "1_1") (pintype "passive"))
      (node (ref "C21") (pin "1") (pinfunction "1_1") (pintype "passive"))
      (node (ref "C22") (pin "1") (pinfunction "1_1") (pintype "passive"))
      (node (ref "C26") (pin "1") (pinfunction "1_1") (pintype "passive"))
      (node (ref "C27") (pin "1") (pinfunction "1_1") (pintype "passive"))
      (node (ref "C28") (pin "1") (pinfunction "1_1") (pintype "passive"))
      (node (ref "C29") (pin "1") (pinfunction "1_1") (pintype "passive"))
      (node (ref "C3") (pin "1") (pinfunction "1_1") (pintype "passive"))
      (node (ref "C30") (pin "1") (pinfunction "1_1") (pintype "passive"))
      (node (ref "C31") (pin "1") (pinfunction "1_1") (pintype "passive"))
      (node (ref "C4") (pin "1") (pinfunction "1_1") (pintype "passive"))
      (node (ref "C5") (pin "1") (pinfunction "1_1") (pintype "passive"))
      (node (ref "C6") (pin "1") (pinfunction "1_1") (pintype "passive"))
      (node (ref "D7") (pin "K") (pinfunction "K_K") (pintype "passive"))
      (node (ref "J1") (pin "1") (pinfunction "1_1") (pintype "passive"))
      (node (ref "P1") (pin "1") (pinfunction "1_1") (pintype "passive"))
      (node (ref "P2") (pin "1") (pinfunction "1_1") (pintype "passive"))
      (node (ref "R14") (pin "1") (pinfunction "1_1") (pintype "passive"))
      (node (ref "R2") (pin "1") (pinfunction "1_1") (pintype "passive"))
      (node (ref "S1") (pin "2") (pinfunction "2_2") (pintype "passive"))
      (node (ref "S2") (pin "2") (pinfunction "2_2") (pintype "passive"))
      (node (ref "U2") (pin "10") (pinfunction "VSS_5_10") (pintype "power_in"))
      (node (ref "U2") (pin "19") (pinfunction "VSSA_19") (pintype "power_in"))
      (node (ref "U2") (pin "27") (pinfunction "VSS_4_27") (pintype "power_in"))
      (node (ref "U2") (pin "49") (pinfunction "VSS_1_49") (pintype "power_in"))
      (node (ref "U2") (pin "74") (pinfunction "VSS_2_74") (pintype "power_in"))
      (node (ref "U2") (pin "99") (pinfunction "VSS_3_99") (pintype "power_in"))
      (node (ref "VR1") (pin "1") (pinfunction "GND_1") (pintype "passive"))
      (node (ref "VR3") (pin "1") (pinfunction "GND_1") (pintype "passive"))
    )
    (net (code "132") (name "Net-(*1-GPIO9)") (class "Default")
      (node (ref "*1") (pin "27") (pinfunction "GPIO9_27") (pintype "passive"))
      (node (ref "D9") (pin "K") (pinfunction "K_K") (pintype "passive"))
    )
    (net (code "133") (name "Net-(*1-GPIO10)") (class "Default")
      (node (ref "*1") (pin "30") (pinfunction "GPIO10_30") (pintype "passive"))
      (node (ref "D8") (pin "K") (pinfunction "K_K") (pintype "passive"))
    )
    (net (code "134") (name "Net-(*1-RST)") (class "Default")
      (node (ref "*1") (pin "4") (pinfunction "RST_4") (pintype "passive"))
      (node (ref "R12") (pin "2") (pinfunction "2_2") (pintype "passive"))
    )
    (net (code "135") (name "Net-(A1-RANGE)") (class "Default")
      (node (ref "A1") (pin "8") (pinfunction "RANGE_8") (pintype "passive"))
      (node (ref "OS1") (pin "1") (pinfunction "1_1") (pintype "passive"))
    )
    (net (code "136") (name "Net-(A1-REFIN{slash}REFOUT)") (class "Default")
      (node (ref "A1") (pin "42") (pinfunction "REFIN/REFOUT_42") (pintype "passive"))
      (node (ref "C25") (pin "1") (pinfunction "1_1") (pintype "passive"))
    )
    (net (code "137") (name "Net-(A1-REF_SELECT)") (class "Default")
      (node (ref "A1") (pin "34") (pinfunction "REF_SELECT_34") (pintype "passive"))
      (node (ref "R13") (pin "1") (pinfunction "1_1") (pintype "passive"))
    )
    (net (code "138") (name "Net-(A1-REGCAP-Pad36)") (class "Default")
      (node (ref "A1") (pin "36") (pinfunction "REGCAP_36") (pintype "passive"))
      (node (ref "C33") (pin "1") (pinfunction "1_1") (pintype "passive"))
    )
    (net (code "139") (name "Net-(A1-REGCAP-Pad39)") (class "Default")
      (node (ref "A1") (pin "39") (pinfunction "REGCAP_39") (pintype "passive"))
      (node (ref "C32") (pin "1") (pinfunction "1_1") (pintype "passive"))
    )
    (net (code "140") (name "Net-(A2-RANGE)") (class "Default")
      (node (ref "A2") (pin "8") (pinfunction "RANGE_8") (pintype "passive"))
      (node (ref "OS6") (pin "1") (pinfunction "1_1") (pintype "passive"))
    )
    (net (code "141") (name "Net-(A2-REFIN{slash}REFOUT)") (class "Default")
      (node (ref "A2") (pin "42") (pinfunction "REFIN/REFOUT_42") (pintype "passive"))
      (node (ref "C41") (pin "1") (pinfunction "1_1") (pintype "passive"))
    )
    (net (code "142") (name "Net-(A2-REF_SELECT)") (class "Default")
      (node (ref "A2") (pin "34") (pinfunction "REF_SELECT_34") (pintype "passive"))
      (node (ref "R17") (pin "1") (pinfunction "1_1") (pintype "passive"))
    )
    (net (code "143") (name "Net-(A2-REGCAP-Pad36)") (class "Default")
      (node (ref "A2") (pin "36") (pinfunction "REGCAP_36") (pintype "passive"))
      (node (ref "C43") (pin "1") (pinfunction "1_1") (pintype "passive"))
    )
    (net (code "144") (name "Net-(A2-REGCAP-Pad39)") (class "Default")
      (node (ref "A2") (pin "39") (pinfunction "REGCAP_39") (pintype "passive"))
      (node (ref "C42") (pin "1") (pinfunction "1_1") (pintype "passive"))
    )
    (net (code "145") (name "Net-(D5-PadA)") (class "Default")
      (node (ref "D5") (pin "A") (pinfunction "A_A") (pintype "passive"))
      (node (ref "R6") (pin "2") (pinfunction "2_2") (pintype "passive"))
    )
    (net (code "146") (name "Net-(D6-K)") (class "Default")
      (node (ref "C10") (pin "2") (pinfunction "2_2") (pintype "passive"))
      (node (ref "D6") (pin "2") (pinfunction "K_2") (pintype "passive"))
      (node (ref "R1") (pin "1") (pinfunction "1_1") (pintype "passive"))
      (node (ref "R4") (pin "2") (pinfunction "2_2") (pintype "passive"))
    )
    (net (code "147") (name "Net-(D7-PadA)") (class "Default")
      (node (ref "D7") (pin "A") (pinfunction "A_A") (pintype "passive"))
      (node (ref "R8") (pin "2") (pinfunction "2_2") (pintype "passive"))
    )
    (net (code "148") (name "Net-(D8-PadA)") (class "Default")
      (node (ref "D8") (pin "A") (pinfunction "A_A") (pintype "passive"))
      (node (ref "R15") (pin "1") (pinfunction "1_1") (pintype "passive"))
    )
    (net (code "149") (name "Net-(D9-PadA)") (class "Default")
      (node (ref "D9") (pin "A") (pinfunction "A_A") (pintype "passive"))
      (node (ref "R16") (pin "2") (pinfunction "2_2") (pintype "passive"))
    )
    (net (code "150") (name "Net-(D10-PadA)") (class "Default")
      (node (ref "D10") (pin "A") (pinfunction "A_A") (pintype "passive"))
      (node (ref "P1") (pin "2") (pinfunction "2_2") (pintype "passive"))
    )
    (net (code "151") (name "Net-(U1--IN)") (class "Default")
      (node (ref "R5") (pin "1") (pinfunction "1_1") (pintype "passive"))
      (node (ref "U1") (pin "4") (pinfunction "-IN_4") (pintype "passive"))
    )
    (net (code "152") (name "Net-(VR2-GND)") (class "Default")
      (node (ref "R2") (pin "2") (pinfunction "2_2") (pintype "passive"))
      (node (ref "R3") (pin "1") (pinfunction "1_1") (pintype "passive"))
      (node (ref "VR2") (pin "1") (pinfunction "GND_1") (pintype "passive"))
    )
    (net (code "153") (name "VCC") (class "Default")
      (node (ref "A1") (pin "23") (pinfunction "VDRIVE_23") (pintype "passive"))
      (node (ref "A2") (pin "23") (pinfunction "VDRIVE_23") (pintype "passive"))
      (node (ref "C13") (pin "2") (pinfunction "2_2") (pintype "passive"))
      (node (ref "C14") (pin "2") (pinfunction "2_2") (pintype "passive"))
      (node (ref "C24") (pin "1") (pinfunction "1_1") (pintype "passive"))
      (node (ref "C26") (pin "2") (pinfunction "2_2") (pintype "passive"))
      (node (ref "C27") (pin "2") (pinfunction "2_2") (pintype "passive"))
      (node (ref "C28") (pin "2") (pinfunction "2_2") (pintype "passive"))
      (node (ref "C29") (pin "2") (pinfunction "2_2") (pintype "passive"))
      (node (ref "C30") (pin "2") (pinfunction "2_2") (pintype "passive"))
      (node (ref "C31") (pin "2") (pinfunction "2_2") (pintype "passive"))
      (node (ref "C40") (pin "1") (pinfunction "1_1") (pintype "passive"))
      (node (ref "J1") (pin "4") (pinfunction "4_4") (pintype "passive"))
      (node (ref "P2") (pin "3") (pinfunction "3_3") (pintype "passive"))
      (node (ref "R10") (pin "2") (pinfunction "2_2") (pintype "passive"))
      (node (ref "R11") (pin "2") (pinfunction "2_2") (pintype "passive"))
      (node (ref "R13") (pin "2") (pinfunction "2_2") (pintype "passive"))
      (node (ref "R17") (pin "2") (pinfunction "2_2") (pintype "passive"))
      (node (ref "R8") (pin "1") (pinfunction "1_1") (pintype "passive"))
      (node (ref "R9") (pin "2") (pinfunction "2_2") (pintype "passive"))
      (node (ref "U2") (pin "100") (pinfunction "VDD_3_100") (pintype "power_in"))
      (node (ref "U2") (pin "11") (pinfunction "VDD_5_11") (pintype "power_in"))
      (node (ref "U2") (pin "22") (pinfunction "VDDA_22") (pintype "power_in"))
      (node (ref "U2") (pin "28") (pinfunction "VDD_4_28") (pintype "power_in"))
      (node (ref "U2") (pin "50") (pinfunction "VDD_1_50") (pintype "power_in"))
      (node (ref "U2") (pin "6") (pinfunction "VBAT_6") (pintype "power_in"))
      (node (ref "U2") (pin "75") (pinfunction "VDD_2_75") (pintype "power_in"))
      (node (ref "VR3") (pin "2") (pinfunction "Vout_2") (pintype "passive"))
    )
    (net (code "154") (name "VCC_E103") (class "Default")
      (node (ref "*1") (pin "10") (pinfunction "VBAS_10") (pintype "passive"))
      (node (ref "C3") (pin "2") (pinfunction "2_2") (pintype "passive"))
      (node (ref "C4") (pin "2") (pinfunction "2_2") (pintype "passive"))
      (node (ref "R12") (pin "1") (pinfunction "1_1") (pintype "passive"))
      (node (ref "R15") (pin "2") (pinfunction "2_2") (pintype "passive"))
      (node (ref "R16") (pin "1") (pinfunction "1_1") (pintype "passive"))
      (node (ref "VR1") (pin "2") (pinfunction "Vout_2") (pintype "passive"))
    )
    (net (code "155") (name "VIN") (class "Default")
      (node (ref "C1") (pin "2") (pinfunction "2_2") (pintype "passive"))
      (node (ref "C11") (pin "2") (pinfunction "2_2") (pintype "passive"))
      (node (ref "C12") (pin "2") (pinfunction "2_2") (pintype "passive"))
      (node (ref "C2") (pin "2") (pinfunction "2_2") (pintype "passive"))
      (node (ref "C5") (pin "2") (pinfunction "2_2") (pintype "passive"))
      (node (ref "C6") (pin "2") (pinfunction "2_2") (pintype "passive"))
      (node (ref "D10") (pin "K") (pinfunction "K_K") (pintype "passive"))
      (node (ref "VR1") (pin "3") (pinfunction "Vin_3") (pintype "passive"))
      (node (ref "VR2") (pin "3") (pinfunction "Vin_3") (pintype "passive"))
      (node (ref "VR3") (pin "3") (pinfunction "Vin_3") (pintype "passive"))
    )
    (net (code "156") (name "unconnected-(*1-GPIO0-Pad15)") (class "Default")
      (node (ref "*1") (pin "15") (pinfunction "GPIO0_15") (pintype "passive"))
    )
    (net (code "157") (name "unconnected-(*1-GPIO3-Pad21)") (class "Default")
      (node (ref "*1") (pin "21") (pinfunction "GPIO3_21") (pintype "passive"))
    )
    (net (code "158") (name "unconnected-(*1-GPIO4-Pad22)") (class "Default")
      (node (ref "*1") (pin "22") (pinfunction "GPIO4_22") (pintype "passive"))
    )
    (net (code "159") (name "unconnected-(*1-GPIO5-Pad23)") (class "Default")
      (node (ref "*1") (pin "23") (pinfunction "GPIO5_23") (pintype "passive"))
    )
    (net (code "160") (name "unconnected-(*1-GPIO6-Pad24)") (class "Default")
      (node (ref "*1") (pin "24") (pinfunction "GPIO6_24") (pintype "passive"))
    )
    (net (code "161") (name "unconnected-(*1-GPIO7-Pad25)") (class "Default")
      (node (ref "*1") (pin "25") (pinfunction "GPIO7_25") (pintype "passive"))
    )
    (net (code "162") (name "unconnected-(*1-GPIO8-Pad26)") (class "Default")
      (node (ref "*1") (pin "26") (pinfunction "GPIO8_26") (pintype "passive"))
    )
    (net (code "163") (name "unconnected-(*1-GPIO11-Pad31)") (class "Default")
      (node (ref "*1") (pin "31") (pinfunction "GPIO11_31") (pintype "passive"))
    )
    (net (code "164") (name "unconnected-(*1-GPIO12-Pad32)") (class "Default")
      (node (ref "*1") (pin "32") (pinfunction "GPIO12_32") (pintype "passive"))
    )
    (net (code "165") (name "unconnected-(*1-GPIO13-Pad33)") (class "Default")
      (node (ref "*1") (pin "33") (pinfunction "GPIO13_33") (pintype "passive"))
    )
    (net (code "166") (name "unconnected-(*1-GPIO14-Pad34)") (class "Default")
      (node (ref "*1") (pin "34") (pinfunction "GPIO14_34") (pintype "passive"))
    )
    (net (code "167") (name "unconnected-(*1-GPIO15-Pad35)") (class "Default")
      (node (ref "*1") (pin "35") (pinfunction "GPIO15_35") (pintype "passive"))
    )
    (net (code "168") (name "unconnected-(*1-GPIO16-Pad36)") (class "Default")
      (node (ref "*1") (pin "36") (pinfunction "GPIO16_36") (pintype "passive"))
    )
    (net (code "169") (name "unconnected-(*1-GPIO17-Pad37)") (class "Default")
      (node (ref "*1") (pin "37") (pinfunction "GPIO17_37") (pintype "passive"))
    )
    (net (code "170") (name "unconnected-(*1-GPIO22-Pad38)") (class "Default")
      (node (ref "*1") (pin "38") (pinfunction "GPIO22_38") (pintype "passive"))
    )
    (net (code "171") (name "unconnected-(*1-GPIO26-Pad2)") (class "Default")
      (node (ref "*1") (pin "2") (pinfunction "GPIO26_2") (pintype "passive"))
    )
    (net (code "172") (name "unconnected-(*1-GPIO27-Pad3)") (class "Default")
      (node (ref "*1") (pin "3") (pinfunction "GPIO27_3") (pintype "passive"))
    )
    (net (code "173") (name "unconnected-(*1-GPIO28-Pad39)") (class "Default")
      (node (ref "*1") (pin "39") (pinfunction "GPIO28_39") (pintype "passive"))
    )
    (net (code "174") (name "unconnected-(*1-GPIO30-Pad18)") (class "Default")
      (node (ref "*1") (pin "18") (pinfunction "GPIO30_18") (pintype "passive"))
    )
    (net (code "175") (name "unconnected-(*1-GPIO31-Pad14)") (class "Default")
      (node (ref "*1") (pin "14") (pinfunction "GPIO31_14") (pintype "passive"))
    )
    (net (code "176") (name "unconnected-(*1-SOP0-Pad7)") (class "Default")
      (node (ref "*1") (pin "7") (pinfunction "SOP0_7") (pintype "passive"))
    )
    (net (code "177") (name "unconnected-(*1-SOP1-Pad6)") (class "Default")
      (node (ref "*1") (pin "6") (pinfunction "SOP1_6") (pintype "passive"))
    )
    (net (code "178") (name "unconnected-(*1-SOP2-Pad5)") (class "Default")
      (node (ref "*1") (pin "5") (pinfunction "SOP2_5") (pintype "passive"))
    )
    (net (code "179") (name "unconnected-(*1-TCK-Pad42)") (class "Default")
      (node (ref "*1") (pin "42") (pinfunction "TCK_42") (pintype "passive"))
    )
    (net (code "180") (name "unconnected-(*1-TDI-Pad40)") (class "Default")
      (node (ref "*1") (pin "40") (pinfunction "TDI_40") (pintype "passive"))
    )
    (net (code "181") (name "unconnected-(*1-TDO-Pad41)") (class "Default")
      (node (ref "*1") (pin "41") (pinfunction "TDO_41") (pintype "passive"))
    )
    (net (code "182") (name "unconnected-(*1-TMS-Pad43)") (class "Default")
      (node (ref "*1") (pin "43") (pinfunction "TMS_43") (pintype "passive"))
    )
    (net (code "183") (name "unconnected-(U2A-OSC_IN-Pad12)") (class "Default")
      (node (ref "U2") (pin "12") (pinfunction "OSC_IN_12") (pintype "input+no_connect"))
    )
    (net (code "184") (name "unconnected-(U2A-OSC_OUT-Pad13)") (class "Default")
      (node (ref "U2") (pin "13") (pinfunction "OSC_OUT_13") (pintype "output+no_connect"))
    )
    (net (code "185") (name "unconnected-(U2A-PA5-Pad30)") (class "Default")
      (node (ref "U2") (pin "30") (pinfunction "PA5_30") (pintype "bidirectional"))
    )
    (net (code "186") (name "unconnected-(U2A-PA6-Pad31)") (class "Default")
      (node (ref "U2") (pin "31") (pinfunction "PA6_31") (pintype "bidirectional"))
    )
    (net (code "187") (name "unconnected-(U2A-PA12-Pad71)") (class "Default")
      (node (ref "U2") (pin "71") (pinfunction "PA12_71") (pintype "bidirectional"))
    )
    (net (code "188") (name "unconnected-(U2A-PA15-Pad77)") (class "Default")
      (node (ref "U2") (pin "77") (pinfunction "PA15_77") (pintype "bidirectional"))
    )
    (net (code "189") (name "unconnected-(U2A-PB10-Pad47)") (class "Default")
      (node (ref "U2") (pin "47") (pinfunction "PB10_47") (pintype "bidirectional"))
    )
    (net (code "190") (name "unconnected-(U2A-PB12-Pad51)") (class "Default")
      (node (ref "U2") (pin "51") (pinfunction "PB12_51") (pintype "bidirectional"))
    )
    (net (code "191") (name "unconnected-(U2A-PB15-Pad54)") (class "Default")
      (node (ref "U2") (pin "54") (pinfunction "PB15_54") (pintype "bidirectional"))
    )
    (net (code "192") (name "unconnected-(U2A-PC10-Pad78)") (class "Default")
      (node (ref "U2") (pin "78") (pinfunction "PC10_78") (pintype "bidirectional"))
    )
    (net (code "193") (name "unconnected-(U2A-PC11-Pad79)") (class "Default")
      (node (ref "U2") (pin "79") (pinfunction "PC11_79") (pintype "bidirectional"))
    )
    (net (code "194") (name "unconnected-(U2A-PC13-TAMPER-RTC-Pad7)") (class "Default")
      (node (ref "U2") (pin "7") (pinfunction "PC13-TAMPER-RTC_7") (pintype "bidirectional+no_connect"))
    )
    (net (code "195") (name "unconnected-(U2A-PC14-OSC32_IN-Pad8)") (class "Default")
      (node (ref "U2") (pin "8") (pinfunction "PC14-OSC32_IN_8") (pintype "bidirectional+no_connect"))
    )
    (net (code "196") (name "unconnected-(U2A-PC15-OSC32_OUT-Pad9)") (class "Default")
      (node (ref "U2") (pin "9") (pinfunction "PC15-OSC32_OUT_9") (pintype "bidirectional+no_connect"))
    )
    (net (code "197") (name "unconnected-(U2B-NC-Pad73)") (class "Default")
      (node (ref "U2") (pin "73") (pinfunction "NC_73") (pintype "passive+no_connect"))
    )
    (net (code "198") (name "unconnected-(U2B-VREF+-Pad21)") (class "Default")
      (node (ref "U2") (pin "21") (pinfunction "VREF+_21") (pintype "power_in+no_connect"))
    )
    (net (code "199") (name "unconnected-(U2B-VREF--Pad20)") (class "Default")
      (node (ref "U2") (pin "20") (pinfunction "VREF-_20") (pintype "power_in+no_connect"))
    )
  )
)
